# io-board-d-2.net
KiCad netlist of a schematic drawn in EAGLE
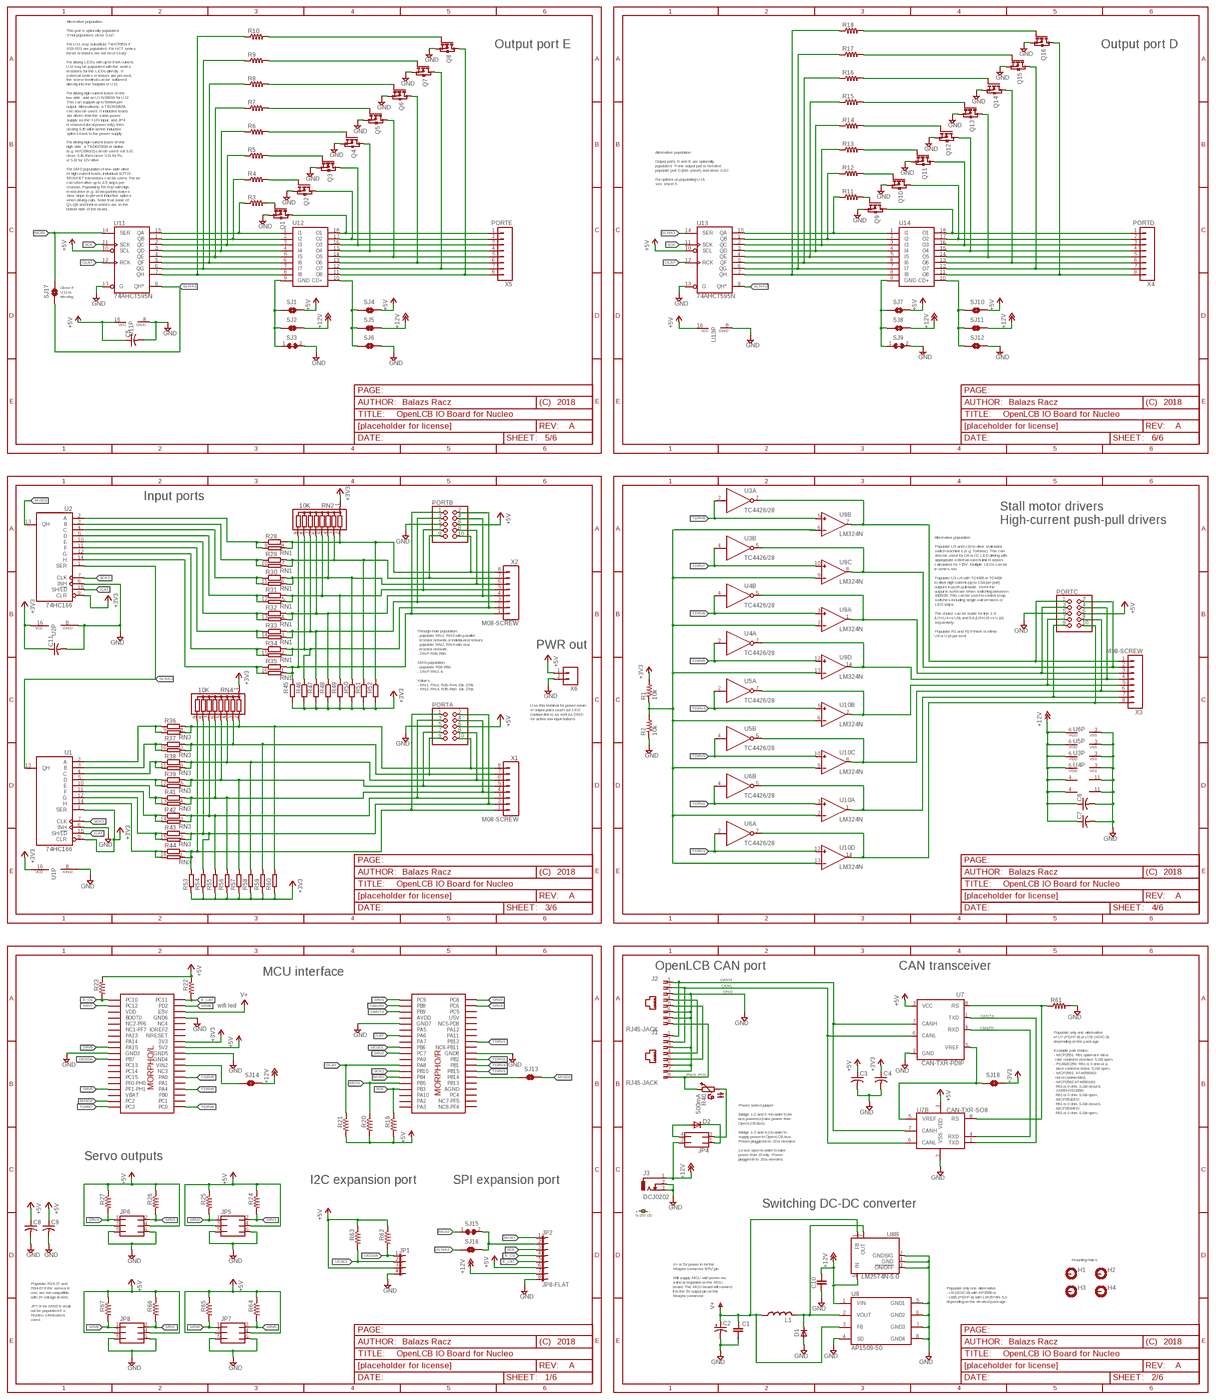
[diagram p0: schematic, sheet 1, overview]
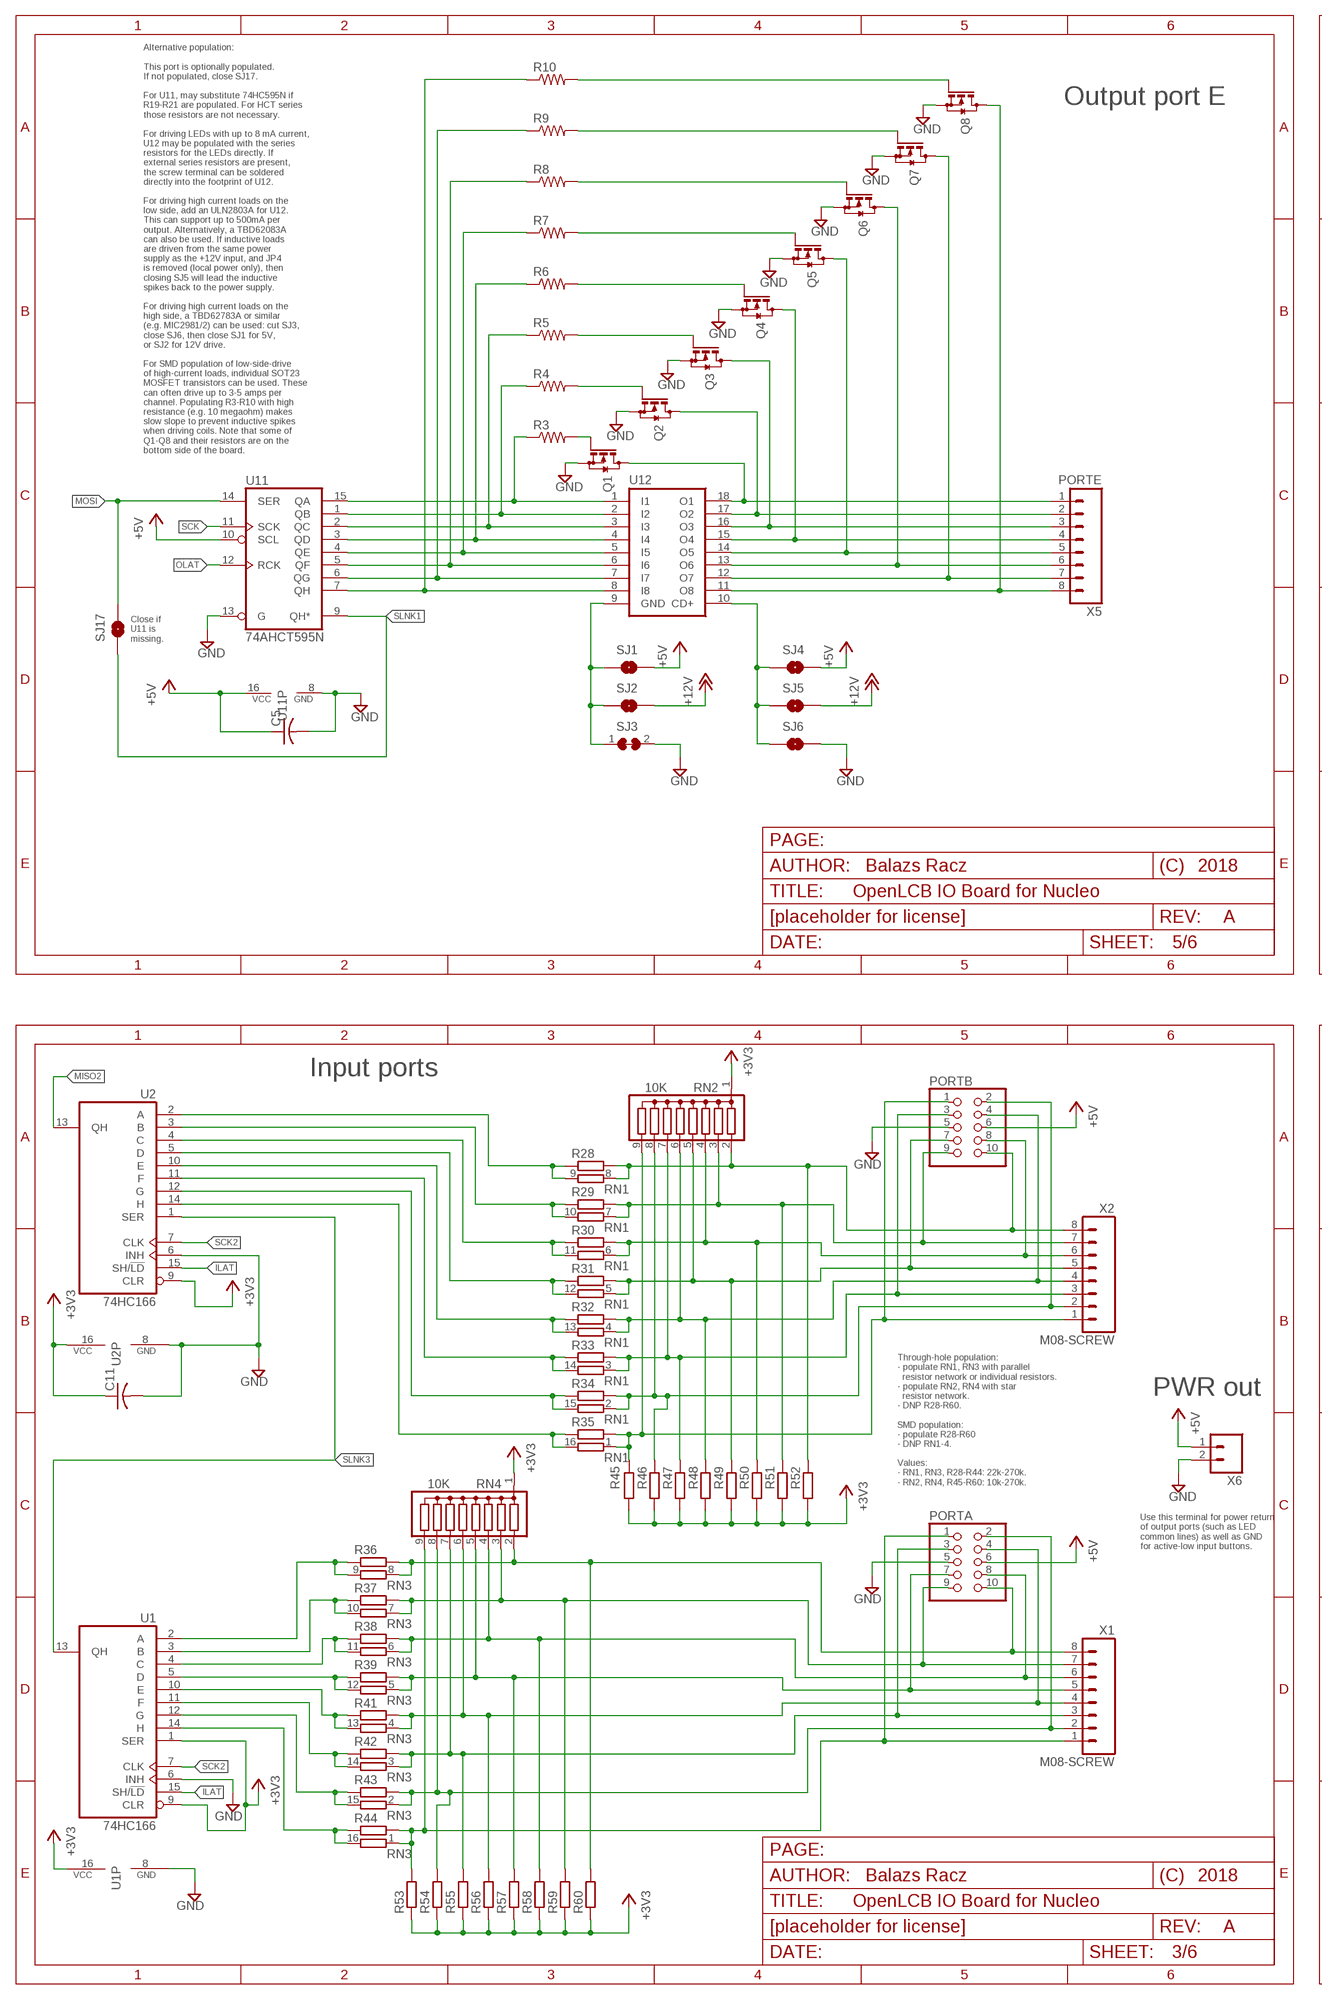
[diagram p1: schematic, sheet 1, part 1 of 4]
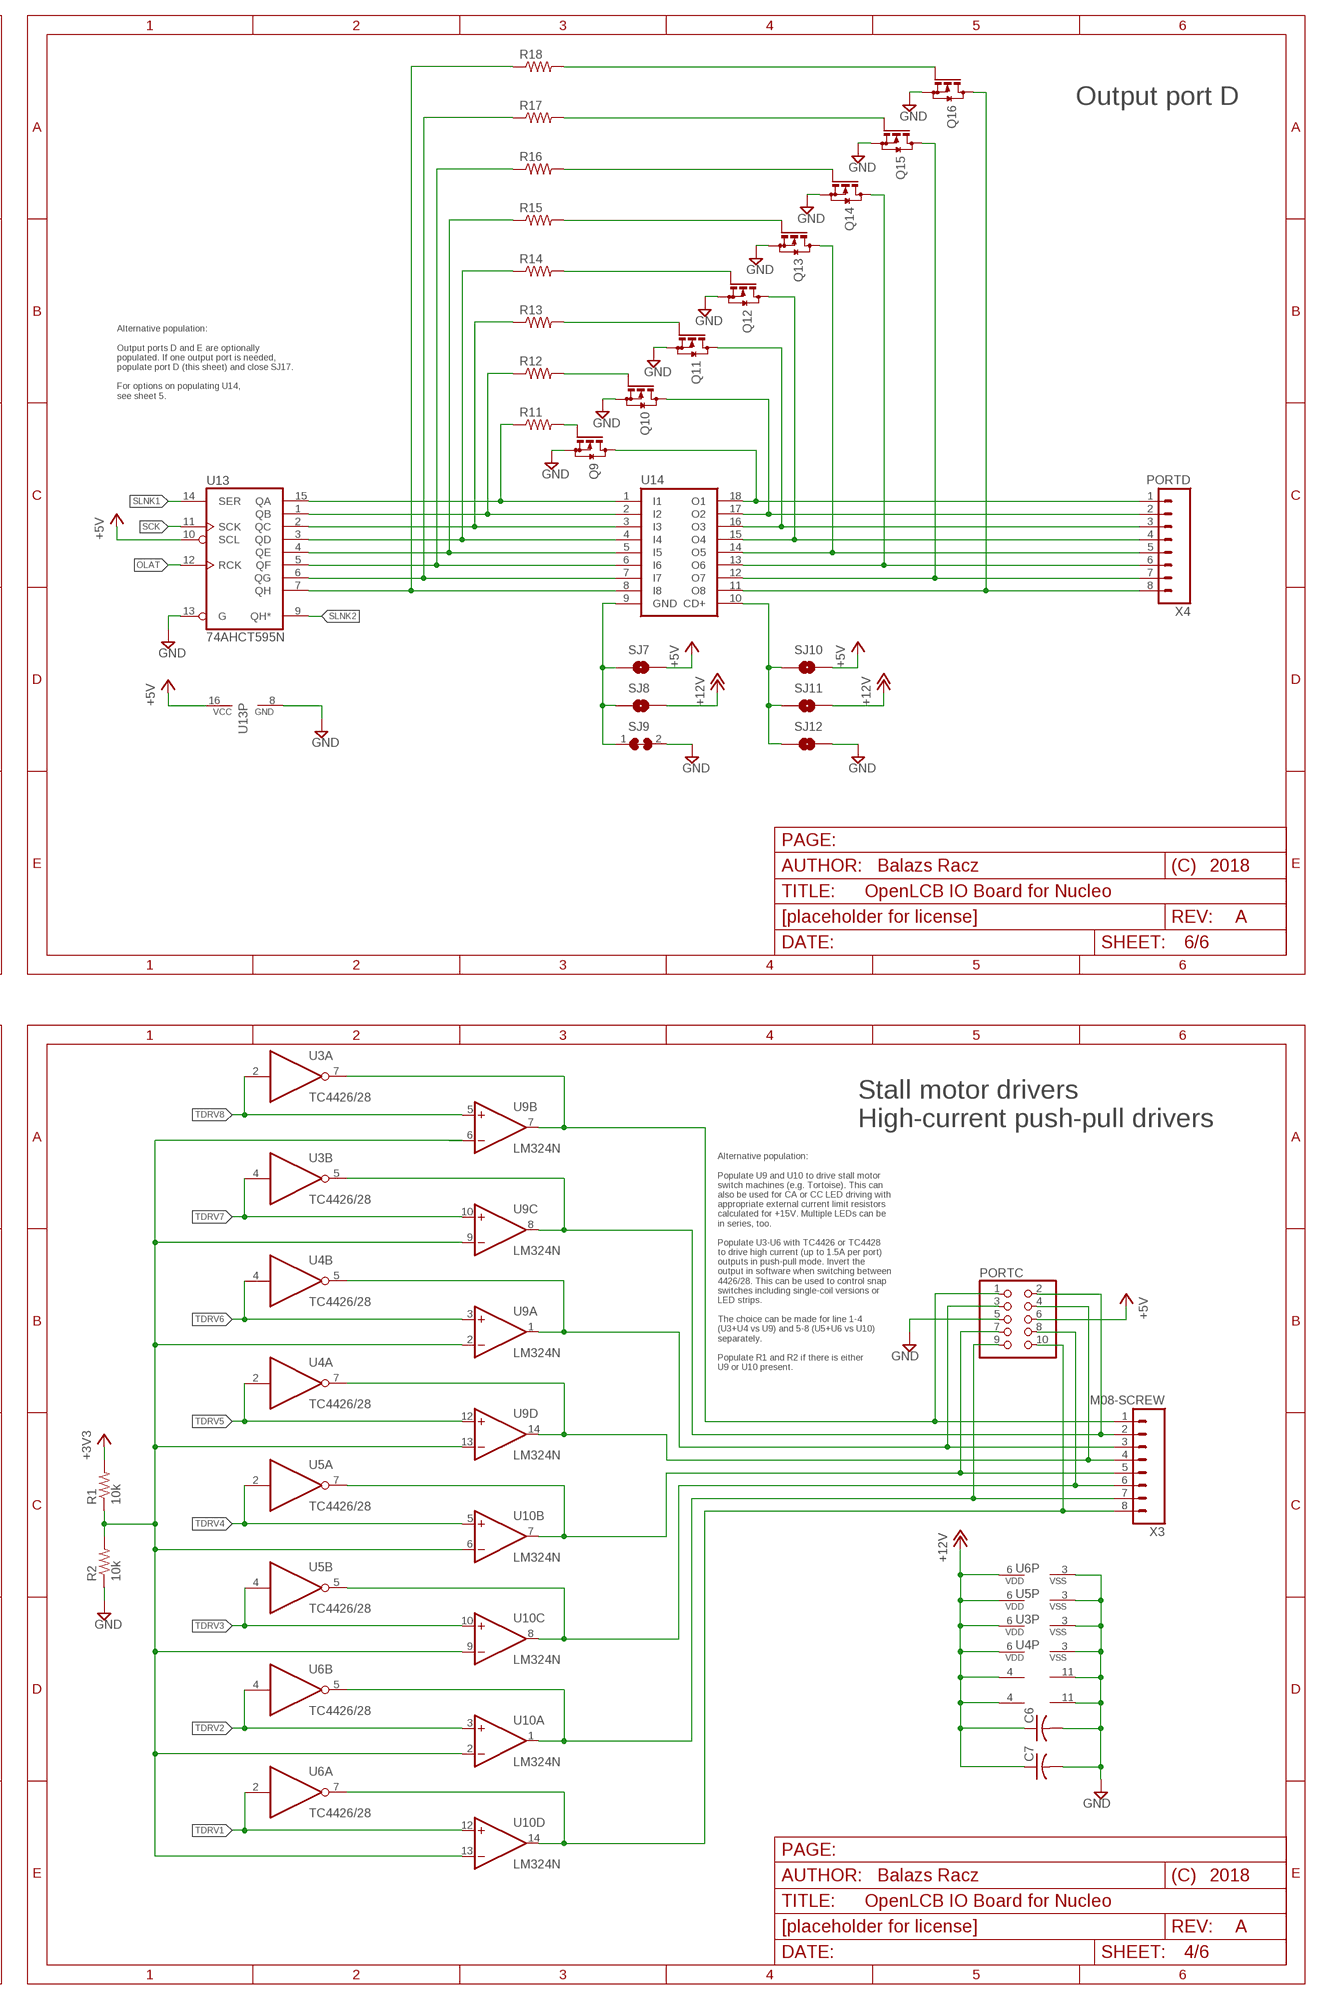
[diagram p2: schematic, sheet 1, part 2 of 4]
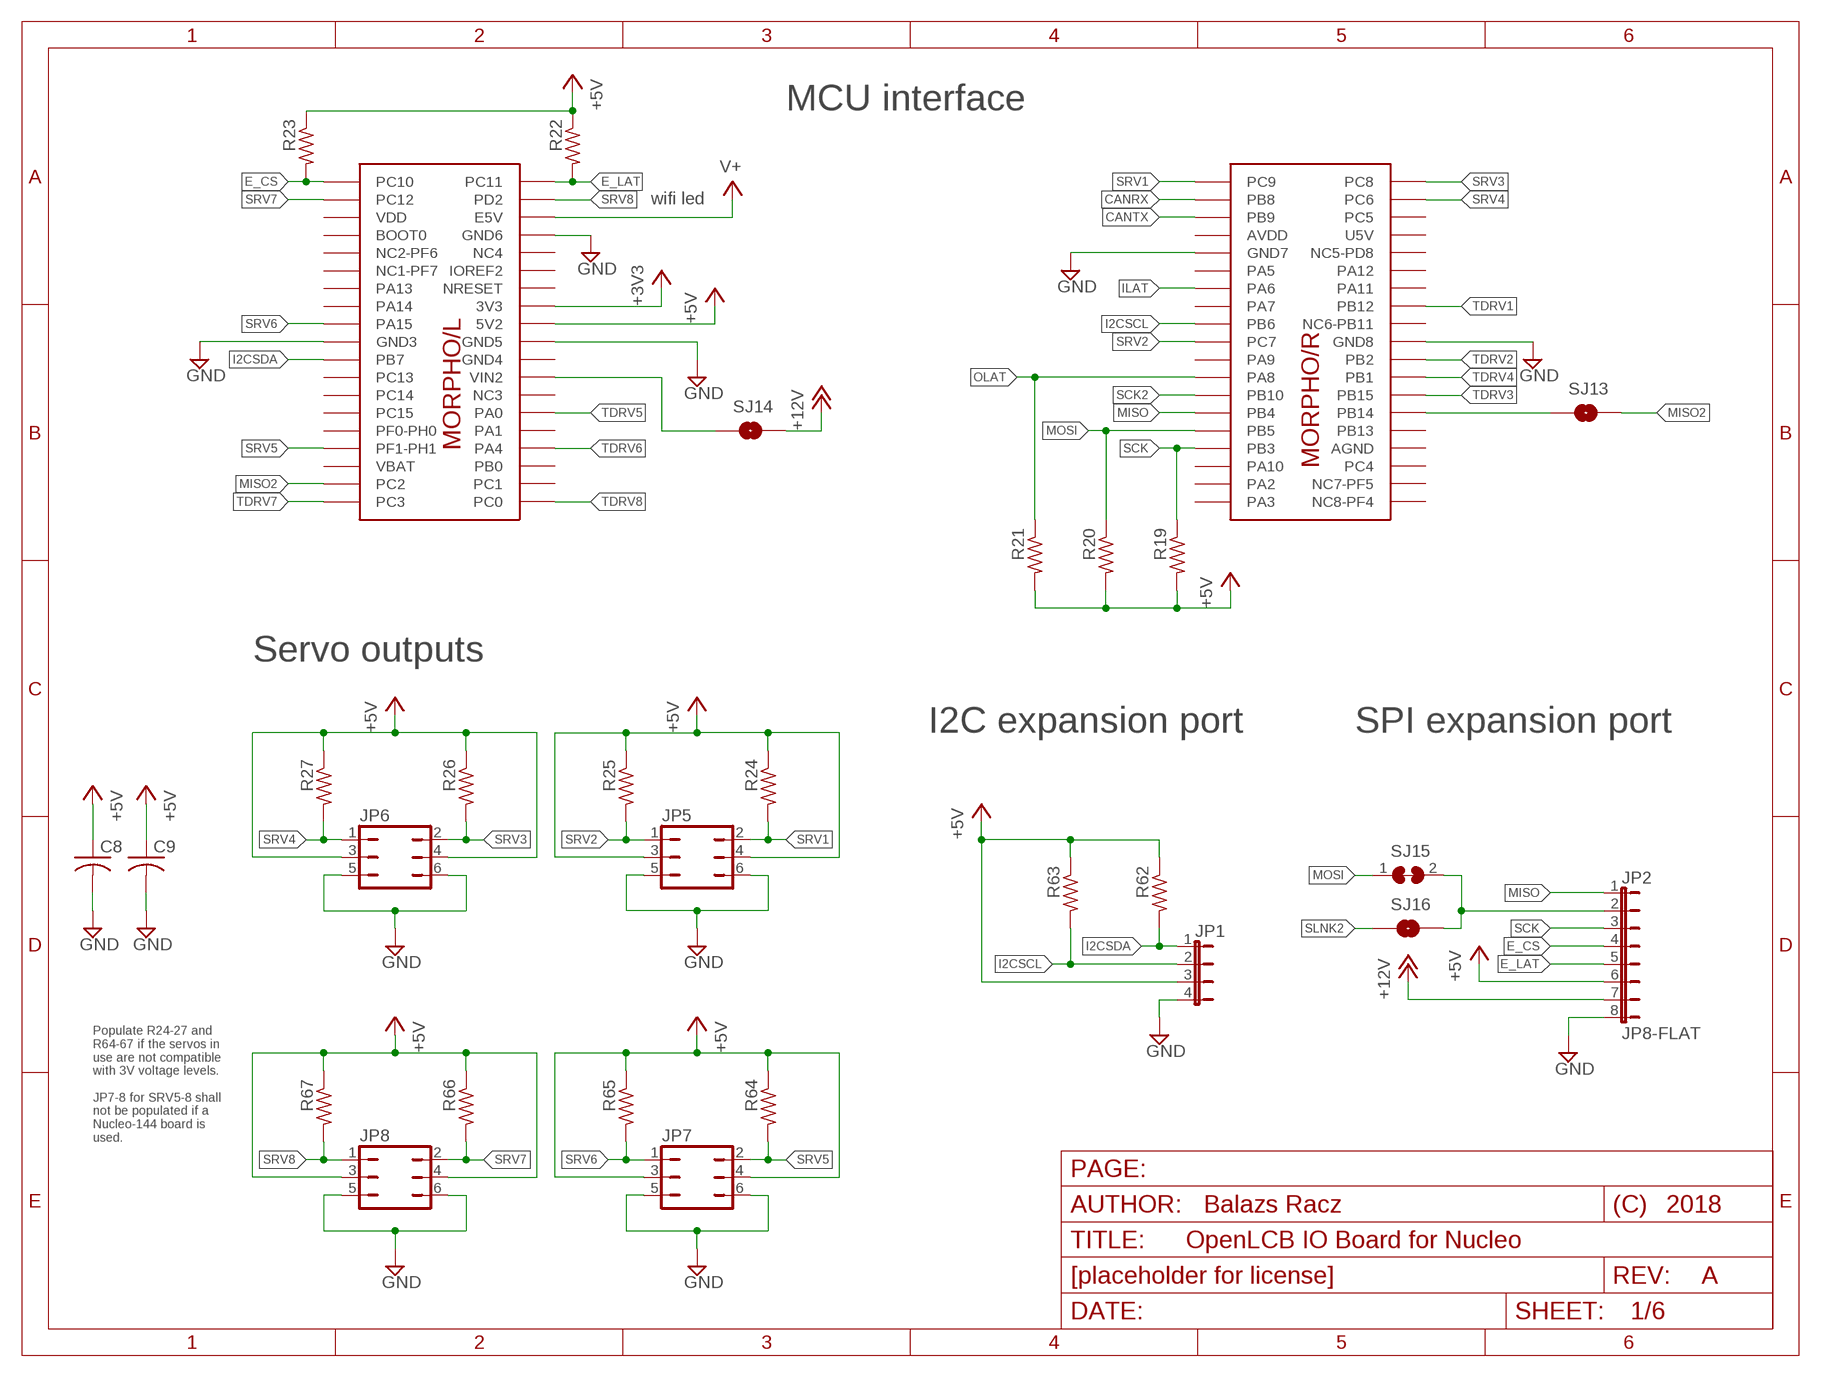
[diagram p3: schematic, sheet 1, part 3 of 4]
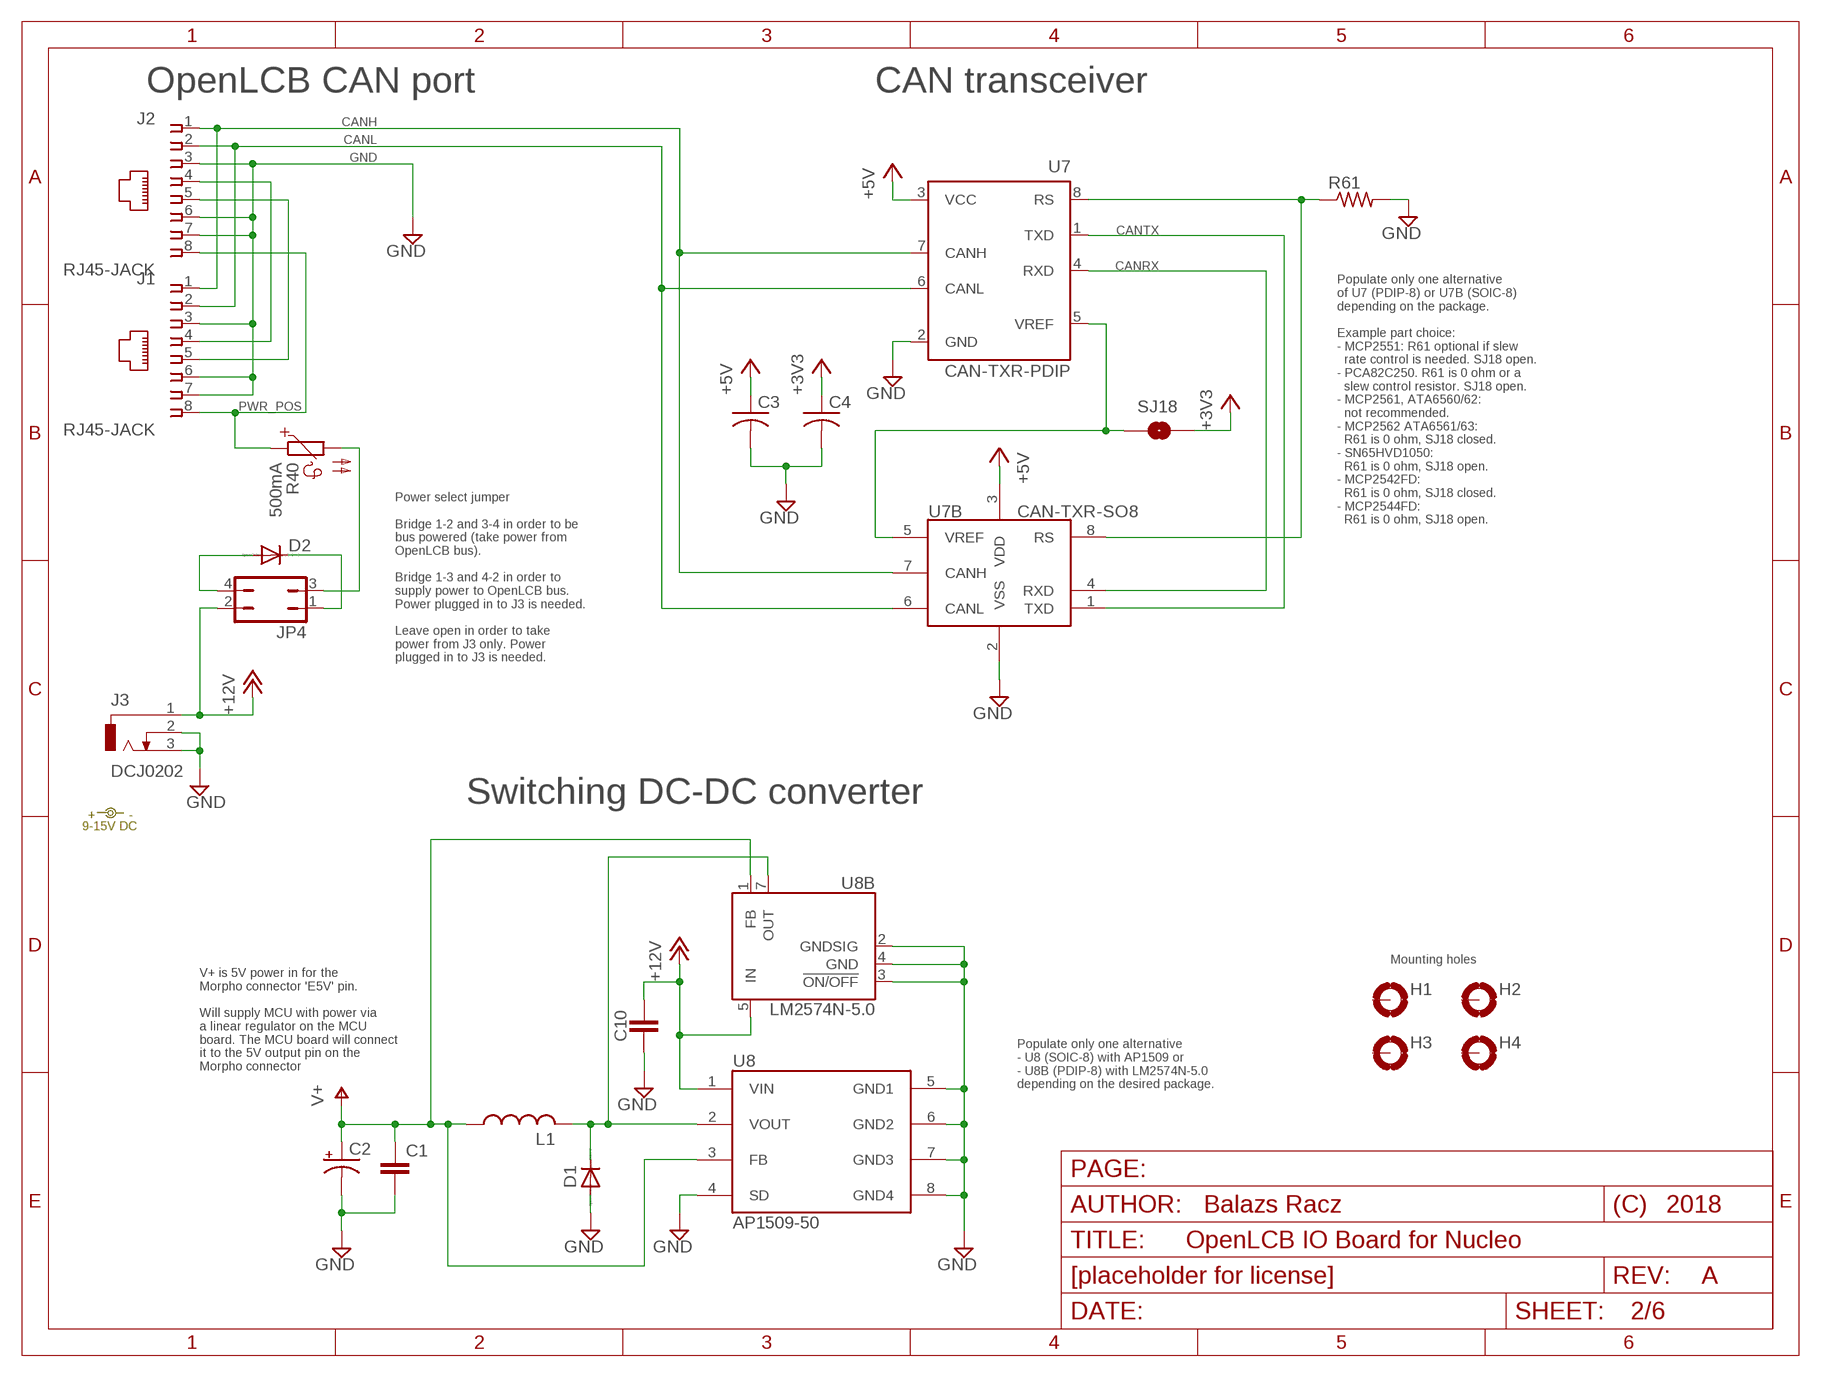
[diagram p4: schematic, sheet 1, part 4 of 4]

(export (version "E")
  (design (tool "Eeschema 10.0.6"))
  (components
    (comp (ref "+12V")
      (value "9-15V DC")
      (footprint "eagle-import:POWER_USAGE")
      (libsource (lib "eagle-import") (part "DOC-POWER_LABEL"))
    )
    (comp (ref "C1")
      (value "C-EUC1206")
      (footprint "eagle-import:C1206")
      (libsource (lib "eagle-import") (part "C-EUC1206"))
    )
    (comp (ref "C2")
      (value "CPOL-USE2.5-5")
      (footprint "eagle-import:E2,5-5")
      (libsource (lib "eagle-import") (part "CPOL-USE2.5-5"))
    )
    (comp (ref "C3")
      (value "C-USC0805")
      (footprint "eagle-import:C0805")
      (libsource (lib "eagle-import") (part "C-USC0805"))
    )
    (comp (ref "C4")
      (value "C-USC0805")
      (footprint "eagle-import:C0805")
      (libsource (lib "eagle-import") (part "C-USC0805"))
    )
    (comp (ref "C5")
      (value "C-USC0805")
      (footprint "eagle-import:C0805")
      (libsource (lib "eagle-import") (part "C-USC0805"))
    )
    (comp (ref "C6")
      (value "C-USC1206")
      (footprint "eagle-import:C1206")
      (libsource (lib "eagle-import") (part "C-USC1206"))
    )
    (comp (ref "C7")
      (value "C-USC1206")
      (footprint "eagle-import:C1206")
      (libsource (lib "eagle-import") (part "C-USC1206"))
    )
    (comp (ref "C8")
      (value "C-USC1206")
      (footprint "eagle-import:C1206")
      (libsource (lib "eagle-import") (part "C-USC1206"))
    )
    (comp (ref "C9")
      (value "C-USC1206")
      (footprint "eagle-import:C1206")
      (libsource (lib "eagle-import") (part "C-USC1206"))
    )
    (comp (ref "C10")
      (value "C-EUC1206")
      (footprint "eagle-import:C1206")
      (libsource (lib "eagle-import") (part "C-EUC1206"))
    )
    (comp (ref "C11")
      (value "C-USC0805")
      (footprint "eagle-import:C0805")
      (libsource (lib "eagle-import") (part "C-USC0805"))
    )
    (comp (ref "D1")
      (value "DIODE-DO41-7.6")
      (footprint "eagle-import:DO41-7.6")
      (libsource (lib "eagle-import") (part "DIODE-DO41-7.6"))
    )
    (comp (ref "D2")
      (value "DIODE-DO41-7.6")
      (footprint "eagle-import:DO41-7.6")
      (libsource (lib "eagle-import") (part "DIODE-DO41-7.6"))
    )
    (comp (ref "H1")
      (value "MOUNT-PAD-ROUND3.3")
      (footprint "eagle-import:3,3-PAD")
      (libsource (lib "eagle-import") (part "MOUNT-PAD-ROUND3.3"))
    )
    (comp (ref "H2")
      (value "MOUNT-PAD-ROUND3.3")
      (footprint "eagle-import:3,3-PAD")
      (libsource (lib "eagle-import") (part "MOUNT-PAD-ROUND3.3"))
    )
    (comp (ref "H3")
      (value "MOUNT-PAD-ROUND3.3")
      (footprint "eagle-import:3,3-PAD")
      (libsource (lib "eagle-import") (part "MOUNT-PAD-ROUND3.3"))
    )
    (comp (ref "H4")
      (value "MOUNT-PAD-ROUND3.3")
      (footprint "eagle-import:3,3-PAD")
      (libsource (lib "eagle-import") (part "MOUNT-PAD-ROUND3.3"))
    )
    (comp (ref "J1")
      (value "RJ45-JACK")
      (footprint "eagle-import:RJ45-PULSE-E5J88")
      (libsource (lib "eagle-import") (part "RJ45-JACKRJ45-PULSE-E5J00"))
    )
    (comp (ref "J2")
      (value "RJ45-JACK")
      (footprint "eagle-import:RJ45-PULSE-E5J88")
      (libsource (lib "eagle-import") (part "RJ45-JACKRJ45-PULSE-E5J00"))
    )
    (comp (ref "J3")
      (value "DCJ0202")
      (footprint "eagle-import:DCJ0202")
      (libsource (lib "eagle-import") (part "DCJ0202"))
    )
    (comp (ref "JP1")
      (value "JP4-FLAT")
      (footprint "eagle-import:JP4F")
      (libsource (lib "eagle-import") (part "JP4-FLAT"))
    )
    (comp (ref "JP2")
      (value "JP8-FLAT")
      (footprint "eagle-import:JP8F")
      (libsource (lib "eagle-import") (part "JP8-FLAT"))
    )
    (comp (ref "JP4")
      (value "JP2Q")
      (footprint "eagle-import:JP2Q")
      (libsource (lib "eagle-import") (part "JP2Q"))
    )
    (comp (ref "JP5")
      (value "JP3Q")
      (footprint "eagle-import:JP3Q")
      (libsource (lib "eagle-import") (part "JP3Q"))
    )
    (comp (ref "JP6")
      (value "JP3Q")
      (footprint "eagle-import:JP3Q")
      (libsource (lib "eagle-import") (part "JP3Q"))
    )
    (comp (ref "JP7")
      (value "JP3Q")
      (footprint "eagle-import:JP3Q")
      (libsource (lib "eagle-import") (part "JP3Q"))
    )
    (comp (ref "JP8")
      (value "JP3Q")
      (footprint "eagle-import:JP3Q")
      (libsource (lib "eagle-import") (part "JP3Q"))
    )
    (comp (ref "L1")
      (value "L-US")
      (footprint "eagle-import:L5-8,5")
      (libsource (lib "eagle-import") (part "L-US"))
    )
    (comp (ref "PORTA")
      (value "PINHD-2X5CN")
      (footprint "eagle-import:CON10M")
      (libsource (lib "eagle-import") (part "PINHD-2X5CN"))
    )
    (comp (ref "PORTB")
      (value "PINHD-2X5CN")
      (footprint "eagle-import:CON10M")
      (libsource (lib "eagle-import") (part "PINHD-2X5CN"))
    )
    (comp (ref "PORTC")
      (value "PINHD-2X5CN")
      (footprint "eagle-import:CON10M")
      (libsource (lib "eagle-import") (part "PINHD-2X5CN"))
    )
    (comp (ref "Q1")
      (value "BSS123")
      (footprint "eagle-import:SOT23")
      (libsource (lib "eagle-import") (part "BSS123"))
    )
    (comp (ref "Q2")
      (value "BSS123")
      (footprint "eagle-import:SOT23")
      (libsource (lib "eagle-import") (part "BSS123"))
    )
    (comp (ref "Q3")
      (value "BSS123")
      (footprint "eagle-import:SOT23")
      (libsource (lib "eagle-import") (part "BSS123"))
    )
    (comp (ref "Q4")
      (value "BSS123")
      (footprint "eagle-import:SOT23")
      (libsource (lib "eagle-import") (part "BSS123"))
    )
    (comp (ref "Q5")
      (value "BSS123")
      (footprint "eagle-import:SOT23")
      (libsource (lib "eagle-import") (part "BSS123"))
    )
    (comp (ref "Q6")
      (value "BSS123")
      (footprint "eagle-import:SOT23")
      (libsource (lib "eagle-import") (part "BSS123"))
    )
    (comp (ref "Q7")
      (value "BSS123")
      (footprint "eagle-import:SOT23")
      (libsource (lib "eagle-import") (part "BSS123"))
    )
    (comp (ref "Q8")
      (value "BSS123")
      (footprint "eagle-import:SOT23")
      (libsource (lib "eagle-import") (part "BSS123"))
    )
    (comp (ref "Q9")
      (value "BSS123")
      (footprint "eagle-import:SOT23")
      (libsource (lib "eagle-import") (part "BSS123"))
    )
    (comp (ref "Q10")
      (value "BSS123")
      (footprint "eagle-import:SOT23")
      (libsource (lib "eagle-import") (part "BSS123"))
    )
    (comp (ref "Q11")
      (value "BSS123")
      (footprint "eagle-import:SOT23")
      (libsource (lib "eagle-import") (part "BSS123"))
    )
    (comp (ref "Q12")
      (value "BSS123")
      (footprint "eagle-import:SOT23")
      (libsource (lib "eagle-import") (part "BSS123"))
    )
    (comp (ref "Q13")
      (value "BSS123")
      (footprint "eagle-import:SOT23")
      (libsource (lib "eagle-import") (part "BSS123"))
    )
    (comp (ref "Q14")
      (value "BSS123")
      (footprint "eagle-import:SOT23")
      (libsource (lib "eagle-import") (part "BSS123"))
    )
    (comp (ref "Q15")
      (value "BSS123")
      (footprint "eagle-import:SOT23")
      (libsource (lib "eagle-import") (part "BSS123"))
    )
    (comp (ref "Q16")
      (value "BSS123")
      (footprint "eagle-import:SOT23")
      (libsource (lib "eagle-import") (part "BSS123"))
    )
    (comp (ref "R1")
      (value "10k")
      (footprint "eagle-import:R0805")
      (libsource (lib "eagle-import") (part "R-US_R0805"))
    )
    (comp (ref "R2")
      (value "10k")
      (footprint "eagle-import:R0805")
      (libsource (lib "eagle-import") (part "R-US_R0805"))
    )
    (comp (ref "R3")
      (value "R-US_R0603")
      (footprint "eagle-import:R0603")
      (libsource (lib "eagle-import") (part "R-US_R0603"))
    )
    (comp (ref "R4")
      (value "R-US_R0603")
      (footprint "eagle-import:R0603")
      (libsource (lib "eagle-import") (part "R-US_R0603"))
    )
    (comp (ref "R5")
      (value "R-US_R0603")
      (footprint "eagle-import:R0603")
      (libsource (lib "eagle-import") (part "R-US_R0603"))
    )
    (comp (ref "R6")
      (value "R-US_R0603")
      (footprint "eagle-import:R0603")
      (libsource (lib "eagle-import") (part "R-US_R0603"))
    )
    (comp (ref "R7")
      (value "R-US_R0603")
      (footprint "eagle-import:R0603")
      (libsource (lib "eagle-import") (part "R-US_R0603"))
    )
    (comp (ref "R8")
      (value "R-US_R0603")
      (footprint "eagle-import:R0603")
      (libsource (lib "eagle-import") (part "R-US_R0603"))
    )
    (comp (ref "R9")
      (value "R-US_R0603")
      (footprint "eagle-import:R0603")
      (libsource (lib "eagle-import") (part "R-US_R0603"))
    )
    (comp (ref "R10")
      (value "R-US_R0603")
      (footprint "eagle-import:R0603")
      (libsource (lib "eagle-import") (part "R-US_R0603"))
    )
    (comp (ref "R11")
      (value "R-US_R0603")
      (footprint "eagle-import:R0603")
      (libsource (lib "eagle-import") (part "R-US_R0603"))
    )
    (comp (ref "R12")
      (value "R-US_R0603")
      (footprint "eagle-import:R0603")
      (libsource (lib "eagle-import") (part "R-US_R0603"))
    )
    (comp (ref "R13")
      (value "R-US_R0603")
      (footprint "eagle-import:R0603")
      (libsource (lib "eagle-import") (part "R-US_R0603"))
    )
    (comp (ref "R14")
      (value "R-US_R0603")
      (footprint "eagle-import:R0603")
      (libsource (lib "eagle-import") (part "R-US_R0603"))
    )
    (comp (ref "R15")
      (value "R-US_R0603")
      (footprint "eagle-import:R0603")
      (libsource (lib "eagle-import") (part "R-US_R0603"))
    )
    (comp (ref "R16")
      (value "R-US_R0603")
      (footprint "eagle-import:R0603")
      (libsource (lib "eagle-import") (part "R-US_R0603"))
    )
    (comp (ref "R17")
      (value "R-US_R0603")
      (footprint "eagle-import:R0603")
      (libsource (lib "eagle-import") (part "R-US_R0603"))
    )
    (comp (ref "R18")
      (value "R-US_R0603")
      (footprint "eagle-import:R0603")
      (libsource (lib "eagle-import") (part "R-US_R0603"))
    )
    (comp (ref "R19")
      (value "R-US_R0805")
      (footprint "eagle-import:R0805")
      (libsource (lib "eagle-import") (part "rcl_334_R-US_R0805"))
    )
    (comp (ref "R20")
      (value "R-US_R0805")
      (footprint "eagle-import:R0805")
      (libsource (lib "eagle-import") (part "rcl_334_R-US_R0805"))
    )
    (comp (ref "R21")
      (value "R-US_R0805")
      (footprint "eagle-import:R0805")
      (libsource (lib "eagle-import") (part "rcl_334_R-US_R0805"))
    )
    (comp (ref "R22")
      (value "R-US_R0805")
      (footprint "eagle-import:R0805")
      (libsource (lib "eagle-import") (part "rcl_334_R-US_R0805"))
    )
    (comp (ref "R23")
      (value "R-US_R0805")
      (footprint "eagle-import:R0805")
      (libsource (lib "eagle-import") (part "rcl_334_R-US_R0805"))
    )
    (comp (ref "R24")
      (value "R-US_R0805")
      (footprint "eagle-import:R0805")
      (libsource (lib "eagle-import") (part "rcl_334_R-US_R0805"))
    )
    (comp (ref "R25")
      (value "R-US_R0805")
      (footprint "eagle-import:R0805")
      (libsource (lib "eagle-import") (part "rcl_334_R-US_R0805"))
    )
    (comp (ref "R26")
      (value "R-US_R0805")
      (footprint "eagle-import:R0805")
      (libsource (lib "eagle-import") (part "rcl_334_R-US_R0805"))
    )
    (comp (ref "R27")
      (value "R-US_R0805")
      (footprint "eagle-import:R0805")
      (libsource (lib "eagle-import") (part "rcl_334_R-US_R0805"))
    )
    (comp (ref "R28")
      (value "R-EU_R0603")
      (footprint "eagle-import:R0603")
      (libsource (lib "eagle-import") (part "R-EU_R0603"))
    )
    (comp (ref "R29")
      (value "R-EU_R0603")
      (footprint "eagle-import:R0603")
      (libsource (lib "eagle-import") (part "R-EU_R0603"))
    )
    (comp (ref "R30")
      (value "R-EU_R0603")
      (footprint "eagle-import:R0603")
      (libsource (lib "eagle-import") (part "R-EU_R0603"))
    )
    (comp (ref "R31")
      (value "R-EU_R0603")
      (footprint "eagle-import:R0603")
      (libsource (lib "eagle-import") (part "R-EU_R0603"))
    )
    (comp (ref "R32")
      (value "R-EU_R0603")
      (footprint "eagle-import:R0603")
      (libsource (lib "eagle-import") (part "R-EU_R0603"))
    )
    (comp (ref "R33")
      (value "R-EU_R0603")
      (footprint "eagle-import:R0603")
      (libsource (lib "eagle-import") (part "R-EU_R0603"))
    )
    (comp (ref "R34")
      (value "R-EU_R0603")
      (footprint "eagle-import:R0603")
      (libsource (lib "eagle-import") (part "R-EU_R0603"))
    )
    (comp (ref "R35")
      (value "R-EU_R0603")
      (footprint "eagle-import:R0603")
      (libsource (lib "eagle-import") (part "R-EU_R0603"))
    )
    (comp (ref "R36")
      (value "R-EU_R0603")
      (footprint "eagle-import:R0603")
      (libsource (lib "eagle-import") (part "R-EU_R0603"))
    )
    (comp (ref "R37")
      (value "R-EU_R0603")
      (footprint "eagle-import:R0603")
      (libsource (lib "eagle-import") (part "R-EU_R0603"))
    )
    (comp (ref "R38")
      (value "R-EU_R0603")
      (footprint "eagle-import:R0603")
      (libsource (lib "eagle-import") (part "R-EU_R0603"))
    )
    (comp (ref "R39")
      (value "R-EU_R0603")
      (footprint "eagle-import:R0603")
      (libsource (lib "eagle-import") (part "R-EU_R0603"))
    )
    (comp (ref "R40")
      (value "500mA")
      (footprint "eagle-import:PTC1812")
      (libsource (lib "eagle-import") (part "PTC_1812"))
    )
    (comp (ref "R41")
      (value "R-EU_R0603")
      (footprint "eagle-import:R0603")
      (libsource (lib "eagle-import") (part "R-EU_R0603"))
    )
    (comp (ref "R42")
      (value "R-EU_R0603")
      (footprint "eagle-import:R0603")
      (libsource (lib "eagle-import") (part "R-EU_R0603"))
    )
    (comp (ref "R43")
      (value "R-EU_R0603")
      (footprint "eagle-import:R0603")
      (libsource (lib "eagle-import") (part "R-EU_R0603"))
    )
    (comp (ref "R44")
      (value "R-EU_R0603")
      (footprint "eagle-import:R0603")
      (libsource (lib "eagle-import") (part "R-EU_R0603"))
    )
    (comp (ref "R45")
      (value "R-EU_R0603")
      (footprint "eagle-import:R0603")
      (libsource (lib "eagle-import") (part "R-EU_R0603"))
    )
    (comp (ref "R46")
      (value "R-EU_R0603")
      (footprint "eagle-import:R0603")
      (libsource (lib "eagle-import") (part "R-EU_R0603"))
    )
    (comp (ref "R47")
      (value "R-EU_R0603")
      (footprint "eagle-import:R0603")
      (libsource (lib "eagle-import") (part "R-EU_R0603"))
    )
    (comp (ref "R48")
      (value "R-EU_R0603")
      (footprint "eagle-import:R0603")
      (libsource (lib "eagle-import") (part "R-EU_R0603"))
    )
    (comp (ref "R49")
      (value "R-EU_R0603")
      (footprint "eagle-import:R0603")
      (libsource (lib "eagle-import") (part "R-EU_R0603"))
    )
    (comp (ref "R50")
      (value "R-EU_R0603")
      (footprint "eagle-import:R0603")
      (libsource (lib "eagle-import") (part "R-EU_R0603"))
    )
    (comp (ref "R51")
      (value "R-EU_R0603")
      (footprint "eagle-import:R0603")
      (libsource (lib "eagle-import") (part "R-EU_R0603"))
    )
    (comp (ref "R52")
      (value "R-EU_R0603")
      (footprint "eagle-import:R0603")
      (libsource (lib "eagle-import") (part "R-EU_R0603"))
    )
    (comp (ref "R53")
      (value "R-EU_R0603")
      (footprint "eagle-import:R0603")
      (libsource (lib "eagle-import") (part "R-EU_R0603"))
    )
    (comp (ref "R54")
      (value "R-EU_R0603")
      (footprint "eagle-import:R0603")
      (libsource (lib "eagle-import") (part "R-EU_R0603"))
    )
    (comp (ref "R55")
      (value "R-EU_R0603")
      (footprint "eagle-import:R0603")
      (libsource (lib "eagle-import") (part "R-EU_R0603"))
    )
    (comp (ref "R56")
      (value "R-EU_R0603")
      (footprint "eagle-import:R0603")
      (libsource (lib "eagle-import") (part "R-EU_R0603"))
    )
    (comp (ref "R57")
      (value "R-EU_R0603")
      (footprint "eagle-import:R0603")
      (libsource (lib "eagle-import") (part "R-EU_R0603"))
    )
    (comp (ref "R58")
      (value "R-EU_R0603")
      (footprint "eagle-import:R0603")
      (libsource (lib "eagle-import") (part "R-EU_R0603"))
    )
    (comp (ref "R59")
      (value "R-EU_R0603")
      (footprint "eagle-import:R0603")
      (libsource (lib "eagle-import") (part "R-EU_R0603"))
    )
    (comp (ref "R60")
      (value "R-EU_R0603")
      (footprint "eagle-import:R0603")
      (libsource (lib "eagle-import") (part "R-EU_R0603"))
    )
    (comp (ref "R61")
      (value "R-US_R0805")
      (footprint "eagle-import:R0805")
      (libsource (lib "eagle-import") (part "rcl_334_R-US_R0805"))
    )
    (comp (ref "R62")
      (value "R-US_R0805")
      (footprint "eagle-import:R0805")
      (libsource (lib "eagle-import") (part "rcl_334_R-US_R0805"))
    )
    (comp (ref "R63")
      (value "R-US_R0805")
      (footprint "eagle-import:R0805")
      (libsource (lib "eagle-import") (part "rcl_334_R-US_R0805"))
    )
    (comp (ref "R64")
      (value "R-US_R0805")
      (footprint "eagle-import:R0805")
      (libsource (lib "eagle-import") (part "rcl_334_R-US_R0805"))
    )
    (comp (ref "R65")
      (value "R-US_R0805")
      (footprint "eagle-import:R0805")
      (libsource (lib "eagle-import") (part "rcl_334_R-US_R0805"))
    )
    (comp (ref "R66")
      (value "R-US_R0805")
      (footprint "eagle-import:R0805")
      (libsource (lib "eagle-import") (part "rcl_334_R-US_R0805"))
    )
    (comp (ref "R67")
      (value "R-US_R0805")
      (footprint "eagle-import:R0805")
      (libsource (lib "eagle-import") (part "rcl_334_R-US_R0805"))
    )
    (comp (ref "RN1")
      (value "8R-P")
      (footprint "eagle-import:DIL16")
      (libsource (lib "eagle-import") (part "8R-P"))
    )
    (comp (ref "RN2")
      (value "10K")
      (footprint "eagle-import:SIL9")
      (libsource (lib "eagle-import") (part "G08R"))
    )
    (comp (ref "RN3")
      (value "8R-P")
      (footprint "eagle-import:DIL16")
      (libsource (lib "eagle-import") (part "8R-P"))
    )
    (comp (ref "RN4")
      (value "10K")
      (footprint "eagle-import:SIL9")
      (libsource (lib "eagle-import") (part "G08R"))
    )
    (comp (ref "SJ1")
      (value "SJRND2")
      (footprint "eagle-import:SJ_RND2")
      (libsource (lib "eagle-import") (part "SJRND2"))
    )
    (comp (ref "SJ2")
      (value "SJRND2")
      (footprint "eagle-import:SJ_RND2")
      (libsource (lib "eagle-import") (part "SJRND2"))
    )
    (comp (ref "SJ3")
      (value "SJ-C")
      (footprint "eagle-import:SJW-C")
      (libsource (lib "eagle-import") (part "SJ-C"))
    )
    (comp (ref "SJ4")
      (value "SJRND2")
      (footprint "eagle-import:SJ_RND2")
      (libsource (lib "eagle-import") (part "SJRND2"))
    )
    (comp (ref "SJ5")
      (value "SJRND2")
      (footprint "eagle-import:SJ_RND2")
      (libsource (lib "eagle-import") (part "SJRND2"))
    )
    (comp (ref "SJ6")
      (value "SJRND2")
      (footprint "eagle-import:SJ_RND2")
      (libsource (lib "eagle-import") (part "SJRND2"))
    )
    (comp (ref "SJ7")
      (value "SJRND2")
      (footprint "eagle-import:SJ_RND2")
      (libsource (lib "eagle-import") (part "SJRND2"))
    )
    (comp (ref "SJ8")
      (value "SJRND2")
      (footprint "eagle-import:SJ_RND2")
      (libsource (lib "eagle-import") (part "SJRND2"))
    )
    (comp (ref "SJ9")
      (value "SJ-C")
      (footprint "eagle-import:SJW-C")
      (libsource (lib "eagle-import") (part "SJ-C"))
    )
    (comp (ref "SJ10")
      (value "SJRND2")
      (footprint "eagle-import:SJ_RND2")
      (libsource (lib "eagle-import") (part "SJRND2"))
    )
    (comp (ref "SJ11")
      (value "SJRND2")
      (footprint "eagle-import:SJ_RND2")
      (libsource (lib "eagle-import") (part "SJRND2"))
    )
    (comp (ref "SJ12")
      (value "SJRND2")
      (footprint "eagle-import:SJ_RND2")
      (libsource (lib "eagle-import") (part "SJRND2"))
    )
    (comp (ref "SJ13")
      (value "SJRND2")
      (footprint "eagle-import:SJ_RND2")
      (libsource (lib "eagle-import") (part "SJRND2"))
    )
    (comp (ref "SJ14")
      (value "SJRND2")
      (footprint "eagle-import:SJ_RND2")
      (libsource (lib "eagle-import") (part "SJRND2"))
    )
    (comp (ref "SJ15")
      (value "SJ-C")
      (footprint "eagle-import:SJW-C")
      (libsource (lib "eagle-import") (part "SJ-C"))
    )
    (comp (ref "SJ16")
      (value "SJRND2")
      (footprint "eagle-import:SJ_RND2")
      (libsource (lib "eagle-import") (part "SJRND2"))
    )
    (comp (ref "SJ17")
      (value "SJRND2")
      (footprint "eagle-import:SJ_RND2")
      (libsource (lib "eagle-import") (part "SJRND2"))
    )
    (comp (ref "SJ18")
      (value "SJRND2")
      (footprint "eagle-import:SJ_RND2")
      (libsource (lib "eagle-import") (part "SJRND2"))
    )
    (comp (ref "U$1")
      (value "NUCLEO_64_GENERIC")
      (footprint "eagle-import:NUCLEO_BRD_BASE64")
      (libsource (lib "eagle-import") (part "NUCLEO_64_GENERIC"))
    )
    (comp (ref "U1")
      (value "74HC166")
      (footprint "eagle-import:DIL16")
      (libsource (lib "eagle-import") (part "74166N"))
    )
    (comp (ref "U2")
      (value "74HC166")
      (footprint "eagle-import:DIL16")
      (libsource (lib "eagle-import") (part "74166N"))
    )
    (comp (ref "U3")
      (value "TC4426/28")
      (footprint "eagle-import:DIL08-LONG")
      (libsource (lib "eagle-import") (part "TC4426APDIP"))
    )
    (comp (ref "U4")
      (value "TC4426/28")
      (footprint "eagle-import:DIL08-LONG")
      (libsource (lib "eagle-import") (part "TC4426APDIP"))
    )
    (comp (ref "U5")
      (value "TC4426/28")
      (footprint "eagle-import:DIL08-LONG")
      (libsource (lib "eagle-import") (part "TC4426APDIP"))
    )
    (comp (ref "U6")
      (value "TC4426/28")
      (footprint "eagle-import:DIL08-LONG")
      (libsource (lib "eagle-import") (part "TC4426APDIP"))
    )
    (comp (ref "U7")
      (value "CAN-TXR-PDIP")
      (footprint "eagle-import:DIL08")
      (libsource (lib "eagle-import") (part "PCA82C250"))
    )
    (comp (ref "U7B")
      (value "CAN-TXR-SO8")
      (footprint "eagle-import:SO-08")
      (libsource (lib "eagle-import") (part "MCP2551-SN"))
    )
    (comp (ref "U8")
      (value "AP1509-50")
      (footprint "eagle-import:SO-08")
      (libsource (lib "eagle-import") (part "AP1509"))
    )
    (comp (ref "U8B")
      (value "LM2574N-5.0")
      (footprint "eagle-import:DIL08")
      (libsource (lib "eagle-import") (part "LM2574?-N5.0"))
    )
    (comp (ref "U9")
      (value "LM324N")
      (footprint "eagle-import:DIL14")
      (libsource (lib "eagle-import") (part "LM324N"))
    )
    (comp (ref "U10")
      (value "LM324N")
      (footprint "eagle-import:DIL14")
      (libsource (lib "eagle-import") (part "LM324N"))
    )
    (comp (ref "U11")
      (value "74AHCT595N")
      (footprint "eagle-import:DIL16")
      (libsource (lib "eagle-import") (part "74595NHCT"))
    )
    (comp (ref "U12")
      (value "ULN2803A")
      (footprint "eagle-import:DIL18-THIN")
      (libsource (lib "eagle-import") (part "ULN2803A"))
    )
    (comp (ref "U13")
      (value "74AHCT595N")
      (footprint "eagle-import:DIL16")
      (libsource (lib "eagle-import") (part "74595NHCT"))
    )
    (comp (ref "U14")
      (value "ULN2803A")
      (footprint "eagle-import:DIL18-THIN")
      (libsource (lib "eagle-import") (part "ULN2803A"))
    )
    (comp (ref "X1")
      (value "M08-SCREW")
      (footprint "eagle-import:1X08_TERMINAL")
      (libsource (lib "eagle-import") (part "M08-SCREW"))
    )
    (comp (ref "X2")
      (value "M08-SCREW")
      (footprint "eagle-import:1X08_TERMINAL")
      (libsource (lib "eagle-import") (part "M08-SCREW"))
    )
    (comp (ref "X3")
      (value "M08-SCREW")
      (footprint "eagle-import:1X08_TERMINAL")
      (libsource (lib "eagle-import") (part "M08-SCREW"))
    )
    (comp (ref "X4")
      (value "PORTD")
      (footprint "eagle-import:1X08_TERMINAL")
      (libsource (lib "eagle-import") (part "M08-SCREW"))
    )
    (comp (ref "X5")
      (value "PORTE")
      (footprint "eagle-import:1X08_TERMINAL")
      (libsource (lib "eagle-import") (part "M08-SCREW"))
    )
    (comp (ref "X6")
      (value "CONNECTOR-M023.5MM-LOCK")
      (footprint "eagle-import:SCREWTERMINAL-3.5MM-2_LOCK")
      (libsource (lib "eagle-import") (part "CONNECTOR-M023.5MM-LOCK"))
    )
  )
  (nets
    (net (code "1") (name "+3V3") (class "Default")
      (node (ref "C11") (pin "1") (pinfunction "1_1") (pintype "passive"))
      (node (ref "C4") (pin "1") (pinfunction "1_1") (pintype "passive"))
      (node (ref "R1") (pin "2") (pinfunction "2_2") (pintype "passive"))
      (node (ref "R45") (pin "1") (pinfunction "1_1") (pintype "passive"))
      (node (ref "R46") (pin "2") (pinfunction "2_2") (pintype "passive"))
      (node (ref "R47") (pin "2") (pinfunction "2_2") (pintype "passive"))
      (node (ref "R48") (pin "2") (pinfunction "2_2") (pintype "passive"))
      (node (ref "R49") (pin "2") (pinfunction "2_2") (pintype "passive"))
      (node (ref "R50") (pin "2") (pinfunction "2_2") (pintype "passive"))
      (node (ref "R51") (pin "2") (pinfunction "2_2") (pintype "passive"))
      (node (ref "R52") (pin "2") (pinfunction "2_2") (pintype "passive"))
      (node (ref "R53") (pin "1") (pinfunction "1_1") (pintype "passive"))
      (node (ref "R54") (pin "1") (pinfunction "1_1") (pintype "passive"))
      (node (ref "R55") (pin "1") (pinfunction "1_1") (pintype "passive"))
      (node (ref "R56") (pin "1") (pinfunction "1_1") (pintype "passive"))
      (node (ref "R57") (pin "1") (pinfunction "1_1") (pintype "passive"))
      (node (ref "R58") (pin "1") (pinfunction "1_1") (pintype "passive"))
      (node (ref "R59") (pin "1") (pinfunction "1_1") (pintype "passive"))
      (node (ref "R60") (pin "1") (pinfunction "1_1") (pintype "passive"))
      (node (ref "RN2") (pin "1") (pinfunction "1_1") (pintype "passive"))
      (node (ref "RN4") (pin "1") (pinfunction "1_1") (pintype "passive"))
      (node (ref "SJ18") (pin "P$1") (pinfunction "1_P$1") (pintype "passive"))
      (node (ref "U$1") (pin "3V3") (pinfunction "3V3_3V3") (pintype "power_in"))
      (node (ref "U1") (pin "1") (pinfunction "SER_1") (pintype "input"))
      (node (ref "U1") (pin "16") (pinfunction "VCC_16") (pintype "power_in"))
      (node (ref "U1") (pin "9") (pinfunction "CLR_9") (pintype "input"))
      (node (ref "U2") (pin "16") (pinfunction "VCC_16") (pintype "power_in"))
      (node (ref "U2") (pin "9") (pinfunction "CLR_9") (pintype "input"))
    )
    (net (code "2") (name "+5V") (class "Default")
      (node (ref "C3") (pin "1") (pinfunction "1_1") (pintype "passive"))
      (node (ref "C5") (pin "1") (pinfunction "1_1") (pintype "passive"))
      (node (ref "C8") (pin "1") (pinfunction "1_1") (pintype "passive"))
      (node (ref "C9") (pin "1") (pinfunction "1_1") (pintype "passive"))
      (node (ref "JP1") (pin "3") (pinfunction "3_3") (pintype "passive"))
      (node (ref "JP2") (pin "6") (pinfunction "6_6") (pintype "passive"))
      (node (ref "JP5") (pin "3") (pinfunction "3_3") (pintype "passive"))
      (node (ref "JP5") (pin "4") (pinfunction "4_4") (pintype "passive"))
      (node (ref "JP6") (pin "3") (pinfunction "3_3") (pintype "passive"))
      (node (ref "JP6") (pin "4") (pinfunction "4_4") (pintype "passive"))
      (node (ref "JP7") (pin "3") (pinfunction "3_3") (pintype "passive"))
      (node (ref "JP7") (pin "4") (pinfunction "4_4") (pintype "passive"))
      (node (ref "JP8") (pin "3") (pinfunction "3_3") (pintype "passive"))
      (node (ref "JP8") (pin "4") (pinfunction "4_4") (pintype "passive"))
      (node (ref "PORTA") (pin "6") (pinfunction "6_6") (pintype "passive"))
      (node (ref "PORTB") (pin "6") (pinfunction "6_6") (pintype "passive"))
      (node (ref "PORTC") (pin "6") (pinfunction "6_6") (pintype "passive"))
      (node (ref "R19") (pin "2") (pinfunction "2_2") (pintype "passive"))
      (node (ref "R20") (pin "2") (pinfunction "2_2") (pintype "passive"))
      (node (ref "R21") (pin "2") (pinfunction "2_2") (pintype "passive"))
      (node (ref "R22") (pin "1") (pinfunction "1_1") (pintype "passive"))
      (node (ref "R23") (pin "1") (pinfunction "1_1") (pintype "passive"))
      (node (ref "R24") (pin "1") (pinfunction "1_1") (pintype "passive"))
      (node (ref "R25") (pin "1") (pinfunction "1_1") (pintype "passive"))
      (node (ref "R26") (pin "1") (pinfunction "1_1") (pintype "passive"))
      (node (ref "R27") (pin "1") (pinfunction "1_1") (pintype "passive"))
      (node (ref "R62") (pin "1") (pinfunction "1_1") (pintype "passive"))
      (node (ref "R63") (pin "1") (pinfunction "1_1") (pintype "passive"))
      (node (ref "R64") (pin "1") (pinfunction "1_1") (pintype "passive"))
      (node (ref "R65") (pin "1") (pinfunction "1_1") (pintype "passive"))
      (node (ref "R66") (pin "1") (pinfunction "1_1") (pintype "passive"))
      (node (ref "R67") (pin "1") (pinfunction "1_1") (pintype "passive"))
      (node (ref "SJ1") (pin "P$2") (pinfunction "2_P$2") (pintype "passive"))
      (node (ref "SJ10") (pin "P$2") (pinfunction "2_P$2") (pintype "passive"))
      (node (ref "SJ4") (pin "P$2") (pinfunction "2_P$2") (pintype "passive"))
      (node (ref "SJ7") (pin "P$2") (pinfunction "2_P$2") (pintype "passive"))
      (node (ref "U$1") (pin "5V2") (pinfunction "5V2_5V2") (pintype "power_in"))
      (node (ref "U11") (pin "10") (pinfunction "SCL_10") (pintype "input"))
      (node (ref "U11") (pin "16") (pinfunction "VCC_16") (pintype "power_in"))
      (node (ref "U13") (pin "10") (pinfunction "SCL_10") (pintype "input"))
      (node (ref "U13") (pin "16") (pinfunction "VCC_16") (pintype "power_in"))
      (node (ref "U7") (pin "3") (pinfunction "VCC_3") (pintype "power_in"))
      (node (ref "U7B") (pin "3") (pinfunction "VDD_3") (pintype "power_in"))
      (node (ref "X6") (pin "1") (pinfunction "1_1") (pintype "passive"))
    )
    (net (code "3") (name "+12V") (class "Default")
      (node (ref "C10") (pin "1") (pinfunction "1_1") (pintype "passive"))
      (node (ref "C6") (pin "1") (pinfunction "1_1") (pintype "passive"))
      (node (ref "C7") (pin "1") (pinfunction "1_1") (pintype "passive"))
      (node (ref "J3") (pin "1") (pinfunction "1_1") (pintype "passive"))
      (node (ref "JP2") (pin "7") (pinfunction "7_7") (pintype "passive"))
      (node (ref "JP4") (pin "2") (pinfunction "2_2") (pintype "passive"))
      (node (ref "SJ11") (pin "P$2") (pinfunction "2_P$2") (pintype "passive"))
      (node (ref "SJ14") (pin "P$2") (pinfunction "2_P$2") (pintype "passive"))
      (node (ref "SJ2") (pin "P$2") (pinfunction "2_P$2") (pintype "passive"))
      (node (ref "SJ5") (pin "P$2") (pinfunction "2_P$2") (pintype "passive"))
      (node (ref "SJ8") (pin "P$2") (pinfunction "2_P$2") (pintype "passive"))
      (node (ref "U10") (pin "4") (pinfunction "V+_4") (pintype "power_in"))
      (node (ref "U3") (pin "6") (pinfunction "VDD_6") (pintype "power_in"))
      (node (ref "U4") (pin "6") (pinfunction "VDD_6") (pintype "power_in"))
      (node (ref "U5") (pin "6") (pinfunction "VDD_6") (pintype "power_in"))
      (node (ref "U6") (pin "6") (pinfunction "VDD_6") (pintype "power_in"))
      (node (ref "U8") (pin "1") (pinfunction "VIN_1") (pintype "bidirectional"))
      (node (ref "U8B") (pin "5") (pinfunction "IN_5") (pintype "input"))
      (node (ref "U9") (pin "4") (pinfunction "V+_4") (pintype "power_in"))
    )
    (net (code "4") (name "/AGND") (class "Default")
      (node (ref "U$1") (pin "AGND") (pinfunction "AGND_AGND") (pintype "power_in"))
    )
    (net (code "5") (name "/AVDD") (class "Default")
      (node (ref "U$1") (pin "AVDD") (pinfunction "AVDD_AVDD") (pintype "power_in"))
    )
    (net (code "6") (name "/CANH") (class "Default")
      (node (ref "J1") (pin "1") (pinfunction "1_1") (pintype "passive"))
      (node (ref "J2") (pin "1") (pinfunction "1_1") (pintype "passive"))
      (node (ref "U7") (pin "7") (pinfunction "CANH_7") (pintype "bidirectional"))
      (node (ref "U7B") (pin "7") (pinfunction "CANH_7") (pintype "bidirectional"))
    )
    (net (code "7") (name "/CANL") (class "Default")
      (node (ref "J1") (pin "2") (pinfunction "2_2") (pintype "passive"))
      (node (ref "J2") (pin "2") (pinfunction "2_2") (pintype "passive"))
      (node (ref "U7") (pin "6") (pinfunction "CANL_6") (pintype "bidirectional"))
      (node (ref "U7B") (pin "6") (pinfunction "CANL_6") (pintype "bidirectional"))
    )
    (net (code "8") (name "/GND4") (class "Default")
      (node (ref "U$1") (pin "GND4") (pinfunction "GND4_GND4") (pintype "power_in"))
    )
    (net (code "9") (name "/PWR_POS") (class "Default")
      (node (ref "J1") (pin "8") (pinfunction "8_8") (pintype "passive"))
      (node (ref "J2") (pin "8") (pinfunction "8_8") (pintype "passive"))
      (node (ref "R40") (pin "1") (pinfunction "1_1") (pintype "passive"))
    )
    (net (code "10") (name "/U5V") (class "Default")
      (node (ref "U$1") (pin "U5V") (pinfunction "U5V_U5V") (pintype "power_in"))
    )
    (net (code "11") (name "/VBAT") (class "Default")
      (node (ref "U$1") (pin "VBAT") (pinfunction "VBAT_VBAT") (pintype "power_in"))
    )
    (net (code "12") (name "/VDD") (class "Default")
      (node (ref "U$1") (pin "VDD") (pinfunction "VDD_VDD") (pintype "power_in"))
    )
    (net (code "13") (name "CANRX") (class "Default")
      (node (ref "U$1") (pin "PB8") (pinfunction "PB8_PB8") (pintype "bidirectional"))
      (node (ref "U7") (pin "4") (pinfunction "RXD_4") (pintype "output"))
      (node (ref "U7B") (pin "4") (pinfunction "RXD_4") (pintype "bidirectional"))
    )
    (net (code "14") (name "CANTX") (class "Default")
      (node (ref "U$1") (pin "PB9") (pinfunction "PB9_PB9") (pintype "bidirectional"))
      (node (ref "U7") (pin "1") (pinfunction "TXD_1") (pintype "input"))
      (node (ref "U7B") (pin "1") (pinfunction "TXD_1") (pintype "bidirectional"))
    )
    (net (code "15") (name "E_CS") (class "Default")
      (node (ref "JP2") (pin "4") (pinfunction "4_4") (pintype "passive"))
      (node (ref "R23") (pin "2") (pinfunction "2_2") (pintype "passive"))
      (node (ref "U$1") (pin "PC10") (pinfunction "PC10_PC10") (pintype "bidirectional"))
    )
    (net (code "16") (name "E_LAT") (class "Default")
      (node (ref "JP2") (pin "5") (pinfunction "5_5") (pintype "passive"))
      (node (ref "R22") (pin "2") (pinfunction "2_2") (pintype "passive"))
      (node (ref "U$1") (pin "PC11") (pinfunction "PC11_PC11") (pintype "bidirectional"))
    )
    (net (code "17") (name "GND") (class "Default")
      (node (ref "C1") (pin "2") (pinfunction "2_2") (pintype "passive"))
      (node (ref "C10") (pin "2") (pinfunction "2_2") (pintype "passive"))
      (node (ref "C11") (pin "2") (pinfunction "2_2") (pintype "passive"))
      (node (ref "C2") (pin "-") (pinfunction "-_-") (pintype "passive"))
      (node (ref "C3") (pin "2") (pinfunction "2_2") (pintype "passive"))
      (node (ref "C4") (pin "2") (pinfunction "2_2") (pintype "passive"))
      (node (ref "C5") (pin "2") (pinfunction "2_2") (pintype "passive"))
      (node (ref "C6") (pin "2") (pinfunction "2_2") (pintype "passive"))
      (node (ref "C7") (pin "2") (pinfunction "2_2") (pintype "passive"))
      (node (ref "C8") (pin "2") (pinfunction "2_2") (pintype "passive"))
      (node (ref "C9") (pin "2") (pinfunction "2_2") (pintype "passive"))
      (node (ref "D1") (pin "A") (pinfunction "A_A") (pintype "passive"))
      (node (ref "J1") (pin "3") (pinfunction "3_3") (pintype "passive"))
      (node (ref "J1") (pin "6") (pinfunction "6_6") (pintype "passive"))
      (node (ref "J1") (pin "7") (pinfunction "7_7") (pintype "passive"))
      (node (ref "J2") (pin "3") (pinfunction "3_3") (pintype "passive"))
      (node (ref "J2") (pin "6") (pinfunction "6_6") (pintype "passive"))
      (node (ref "J2") (pin "7") (pinfunction "7_7") (pintype "passive"))
      (node (ref "J3") (pin "2") (pinfunction "2_2") (pintype "passive"))
      (node (ref "J3") (pin "3") (pinfunction "3_3") (pintype "passive"))
      (node (ref "JP1") (pin "4") (pinfunction "4_4") (pintype "passive"))
      (node (ref "JP2") (pin "8") (pinfunction "8_8") (pintype "passive"))
      (node (ref "JP5") (pin "5") (pinfunction "5_5") (pintype "passive"))
      (node (ref "JP5") (pin "6") (pinfunction "6_6") (pintype "passive"))
      (node (ref "JP6") (pin "5") (pinfunction "5_5") (pintype "passive"))
      (node (ref "JP6") (pin "6") (pinfunction "6_6") (pintype "passive"))
      (node (ref "JP7") (pin "5") (pinfunction "5_5") (pintype "passive"))
      (node (ref "JP7") (pin "6") (pinfunction "6_6") (pintype "passive"))
      (node (ref "JP8") (pin "5") (pinfunction "5_5") (pintype "passive"))
      (node (ref "JP8") (pin "6") (pinfunction "6_6") (pintype "passive"))
      (node (ref "PORTA") (pin "5") (pinfunction "5_5") (pintype "passive"))
      (node (ref "PORTB") (pin "5") (pinfunction "5_5") (pintype "passive"))
      (node (ref "PORTC") (pin "5") (pinfunction "5_5") (pintype "passive"))
      (node (ref "Q1") (pin "2") (pinfunction "S_2") (pintype "passive"))
      (node (ref "Q10") (pin "2") (pinfunction "S_2") (pintype "passive"))
      (node (ref "Q11") (pin "2") (pinfunction "S_2") (pintype "passive"))
      (node (ref "Q12") (pin "2") (pinfunction "S_2") (pintype "passive"))
      (node (ref "Q13") (pin "2") (pinfunction "S_2") (pintype "passive"))
      (node (ref "Q14") (pin "2") (pinfunction "S_2") (pintype "passive"))
      (node (ref "Q15") (pin "2") (pinfunction "S_2") (pintype "passive"))
      (node (ref "Q16") (pin "2") (pinfunction "S_2") (pintype "passive"))
      (node (ref "Q2") (pin "2") (pinfunction "S_2") (pintype "passive"))
      (node (ref "Q3") (pin "2") (pinfunction "S_2") (pintype "passive"))
      (node (ref "Q4") (pin "2") (pinfunction "S_2") (pintype "passive"))
      (node (ref "Q5") (pin "2") (pinfunction "S_2") (pintype "passive"))
      (node (ref "Q6") (pin "2") (pinfunction "S_2") (pintype "passive"))
      (node (ref "Q7") (pin "2") (pinfunction "S_2") (pintype "passive"))
      (node (ref "Q8") (pin "2") (pinfunction "S_2") (pintype "passive"))
      (node (ref "Q9") (pin "2") (pinfunction "S_2") (pintype "passive"))
      (node (ref "R2") (pin "1") (pinfunction "1_1") (pintype "passive"))
      (node (ref "R61") (pin "2") (pinfunction "2_2") (pintype "passive"))
      (node (ref "SJ12") (pin "P$2") (pinfunction "2_P$2") (pintype "passive"))
      (node (ref "SJ3") (pin "2") (pinfunction "2_2") (pintype "passive"))
      (node (ref "SJ6") (pin "P$2") (pinfunction "2_P$2") (pintype "passive"))
      (node (ref "SJ9") (pin "2") (pinfunction "2_2") (pintype "passive"))
      (node (ref "U$1") (pin "GND3") (pinfunction "GND3_GND3") (pintype "power_in"))
      (node (ref "U$1") (pin "GND5") (pinfunction "GND5_GND5") (pintype "power_in"))
      (node (ref "U$1") (pin "GND6") (pinfunction "GND6_GND6") (pintype "power_in"))
      (node (ref "U$1") (pin "GND7") (pinfunction "GND7_GND7") (pintype "power_in"))
      (node (ref "U$1") (pin "GND8") (pinfunction "GND8_GND8") (pintype "power_in"))
      (node (ref "U1") (pin "6") (pinfunction "INH_6") (pintype "input"))
      (node (ref "U1") (pin "8") (pinfunction "GND_8") (pintype "power_in"))
      (node (ref "U10") (pin "11") (pinfunction "V-_11") (pintype "power_in"))
      (node (ref "U11") (pin "13") (pinfunction "G_13") (pintype "input"))
      (node (ref "U11") (pin "8") (pinfunction "GND_8") (pintype "power_in"))
      (node (ref "U13") (pin "13") (pinfunction "G_13") (pintype "input"))
      (node (ref "U13") (pin "8") (pinfunction "GND_8") (pintype "power_in"))
      (node (ref "U2") (pin "6") (pinfunction "INH_6") (pintype "input"))
      (node (ref "U2") (pin "8") (pinfunction "GND_8") (pintype "power_in"))
      (node (ref "U3") (pin "3") (pinfunction "VSS_3") (pintype "power_in"))
      (node (ref "U4") (pin "3") (pinfunction "VSS_3") (pintype "power_in"))
      (node (ref "U5") (pin "3") (pinfunction "VSS_3") (pintype "power_in"))
      (node (ref "U6") (pin "3") (pinfunction "VSS_3") (pintype "power_in"))
      (node (ref "U7") (pin "2") (pinfunction "GND_2") (pintype "power_in"))
      (node (ref "U7B") (pin "2") (pinfunction "VSS_2") (pintype "power_in"))
      (node (ref "U8") (pin "4") (pinfunction "SD_4") (pintype "bidirectional"))
      (node (ref "U8") (pin "5") (pinfunction "GND1_5") (pintype "power_in"))
      (node (ref "U8") (pin "6") (pinfunction "GND2_6") (pintype "power_in"))
      (node (ref "U8") (pin "7") (pinfunction "GND3_7") (pintype "power_in"))
      (node (ref "U8") (pin "8") (pinfunction "GND4_8") (pintype "power_in"))
      (node (ref "U8B") (pin "2") (pinfunction "GNDSIG_2") (pintype "input"))
      (node (ref "U8B") (pin "3") (pinfunction "~{ON/OFF}_3") (pintype "input"))
      (node (ref "U8B") (pin "4") (pinfunction "GND_4") (pintype "power_in"))
      (node (ref "U9") (pin "11") (pinfunction "V-_11") (pintype "power_in"))
      (node (ref "X6") (pin "2") (pinfunction "2_2") (pintype "passive"))
    )
    (net (code "18") (name "I2CSCL") (class "Default")
      (node (ref "JP1") (pin "2") (pinfunction "2_2") (pintype "passive"))
      (node (ref "R63") (pin "2") (pinfunction "2_2") (pintype "passive"))
      (node (ref "U$1") (pin "PB6") (pinfunction "PB6_PB6") (pintype "bidirectional"))
    )
    (net (code "19") (name "I2CSDA") (class "Default")
      (node (ref "JP1") (pin "1") (pinfunction "1_1") (pintype "passive"))
      (node (ref "R62") (pin "2") (pinfunction "2_2") (pintype "passive"))
      (node (ref "U$1") (pin "PB7") (pinfunction "PB7_PB7") (pintype "bidirectional"))
    )
    (net (code "20") (name "ILAT") (class "Default")
      (node (ref "U$1") (pin "PA6") (pinfunction "PA6_PA6") (pintype "bidirectional"))
      (node (ref "U1") (pin "15") (pinfunction "SH/~{LD}_15") (pintype "input"))
      (node (ref "U2") (pin "15") (pinfunction "SH/~{LD}_15") (pintype "input"))
    )
    (net (code "21") (name "MISO") (class "Default")
      (node (ref "JP2") (pin "1") (pinfunction "1_1") (pintype "passive"))
      (node (ref "U$1") (pin "PB4") (pinfunction "PB4_PB4") (pintype "bidirectional"))
    )
    (net (code "22") (name "MISO2") (class "Default")
      (node (ref "SJ13") (pin "P$2") (pinfunction "2_P$2") (pintype "passive"))
      (node (ref "U$1") (pin "PC2") (pinfunction "PC2_PC2") (pintype "bidirectional"))
      (node (ref "U2") (pin "13") (pinfunction "QH_13") (pintype "output"))
    )
    (net (code "23") (name "MOSI") (class "Default")
      (node (ref "R20") (pin "1") (pinfunction "1_1") (pintype "passive"))
      (node (ref "SJ15") (pin "1") (pinfunction "1_1") (pintype "passive"))
      (node (ref "SJ17") (pin "P$2") (pinfunction "2_P$2") (pintype "passive"))
      (node (ref "U$1") (pin "PB5") (pinfunction "PB5_PB5") (pintype "bidirectional"))
      (node (ref "U11") (pin "14") (pinfunction "SER_14") (pintype "input"))
    )
    (net (code "24") (name "Net-(D2-PadA)") (class "Default")
      (node (ref "D2") (pin "A") (pinfunction "A_A") (pintype "passive"))
      (node (ref "JP4") (pin "4") (pinfunction "4_4") (pintype "passive"))
    )
    (net (code "25") (name "Net-(D2-PadC)") (class "Default")
      (node (ref "D2") (pin "C") (pinfunction "C_C") (pintype "passive"))
      (node (ref "JP4") (pin "1") (pinfunction "1_1") (pintype "passive"))
    )
    (net (code "26") (name "Net-(J1-Pad4)") (class "Default")
      (node (ref "J1") (pin "4") (pinfunction "4_4") (pintype "passive"))
      (node (ref "J2") (pin "4") (pinfunction "4_4") (pintype "passive"))
    )
    (net (code "27") (name "Net-(J1-Pad5)") (class "Default")
      (node (ref "J1") (pin "5") (pinfunction "5_5") (pintype "passive"))
      (node (ref "J2") (pin "5") (pinfunction "5_5") (pintype "passive"))
    )
    (net (code "28") (name "Net-(JP4-Pad3)") (class "Default")
      (node (ref "JP4") (pin "3") (pinfunction "3_3") (pintype "passive"))
      (node (ref "R40") (pin "2") (pinfunction "2_2") (pintype "passive"))
    )
    (net (code "29") (name "Net-(PORTA-Pad1)") (class "Default")
      (node (ref "PORTA") (pin "1") (pinfunction "1_1") (pintype "passive"))
      (node (ref "R44") (pin "2") (pinfunction "2_2") (pintype "passive"))
      (node (ref "R53") (pin "2") (pinfunction "2_2") (pintype "passive"))
      (node (ref "RN3") (pin "1") (pinfunction "1_1") (pintype "passive"))
      (node (ref "RN4") (pin "9") (pinfunction "9_9") (pintype "passive"))
      (node (ref "X1") (pin "1") (pinfunction "1_1") (pintype "passive"))
    )
    (net (code "30") (name "Net-(PORTB-Pad1)") (class "Default")
      (node (ref "PORTB") (pin "1") (pinfunction "1_1") (pintype "passive"))
      (node (ref "R35") (pin "2") (pinfunction "2_2") (pintype "passive"))
      (node (ref "R45") (pin "2") (pinfunction "2_2") (pintype "passive"))
      (node (ref "RN1") (pin "1") (pinfunction "1_1") (pintype "passive"))
      (node (ref "RN2") (pin "9") (pinfunction "9_9") (pintype "passive"))
      (node (ref "X2") (pin "1") (pinfunction "1_1") (pintype "passive"))
    )
    (net (code "31") (name "Net-(Q1-D)") (class "Default")
      (node (ref "Q1") (pin "3") (pinfunction "D_3") (pintype "passive"))
      (node (ref "U12") (pin "18") (pinfunction "O1_18") (pintype "open_collector"))
      (node (ref "X5") (pin "1") (pinfunction "1_1") (pintype "passive"))
    )
    (net (code "32") (name "Net-(Q1-G)") (class "Default")
      (node (ref "Q1") (pin "1") (pinfunction "G_1") (pintype "passive"))
      (node (ref "R3") (pin "2") (pinfunction "2_2") (pintype "passive"))
    )
    (net (code "33") (name "Net-(Q2-D)") (class "Default")
      (node (ref "Q2") (pin "3") (pinfunction "D_3") (pintype "passive"))
      (node (ref "U12") (pin "17") (pinfunction "O2_17") (pintype "open_collector"))
      (node (ref "X5") (pin "2") (pinfunction "2_2") (pintype "passive"))
    )
    (net (code "34") (name "Net-(Q2-G)") (class "Default")
      (node (ref "Q2") (pin "1") (pinfunction "G_1") (pintype "passive"))
      (node (ref "R4") (pin "2") (pinfunction "2_2") (pintype "passive"))
    )
    (net (code "35") (name "Net-(Q3-D)") (class "Default")
      (node (ref "Q3") (pin "3") (pinfunction "D_3") (pintype "passive"))
      (node (ref "U12") (pin "16") (pinfunction "O3_16") (pintype "open_collector"))
      (node (ref "X5") (pin "3") (pinfunction "3_3") (pintype "passive"))
    )
    (net (code "36") (name "Net-(Q3-G)") (class "Default")
      (node (ref "Q3") (pin "1") (pinfunction "G_1") (pintype "passive"))
      (node (ref "R5") (pin "2") (pinfunction "2_2") (pintype "passive"))
    )
    (net (code "37") (name "Net-(Q4-D)") (class "Default")
      (node (ref "Q4") (pin "3") (pinfunction "D_3") (pintype "passive"))
      (node (ref "U12") (pin "15") (pinfunction "O4_15") (pintype "open_collector"))
      (node (ref "X5") (pin "4") (pinfunction "4_4") (pintype "passive"))
    )
    (net (code "38") (name "Net-(Q4-G)") (class "Default")
      (node (ref "Q4") (pin "1") (pinfunction "G_1") (pintype "passive"))
      (node (ref "R6") (pin "2") (pinfunction "2_2") (pintype "passive"))
    )
    (net (code "39") (name "Net-(Q5-D)") (class "Default")
      (node (ref "Q5") (pin "3") (pinfunction "D_3") (pintype "passive"))
      (node (ref "U12") (pin "14") (pinfunction "O5_14") (pintype "open_collector"))
      (node (ref "X5") (pin "5") (pinfunction "5_5") (pintype "passive"))
    )
    (net (code "40") (name "Net-(Q5-G)") (class "Default")
      (node (ref "Q5") (pin "1") (pinfunction "G_1") (pintype "passive"))
      (node (ref "R7") (pin "2") (pinfunction "2_2") (pintype "passive"))
    )
    (net (code "41") (name "Net-(Q6-D)") (class "Default")
      (node (ref "Q6") (pin "3") (pinfunction "D_3") (pintype "passive"))
      (node (ref "U12") (pin "13") (pinfunction "O6_13") (pintype "open_collector"))
      (node (ref "X5") (pin "6") (pinfunction "6_6") (pintype "passive"))
    )
    (net (code "42") (name "Net-(Q6-G)") (class "Default")
      (node (ref "Q6") (pin "1") (pinfunction "G_1") (pintype "passive"))
      (node (ref "R8") (pin "2") (pinfunction "2_2") (pintype "passive"))
    )
    (net (code "43") (name "Net-(Q7-D)") (class "Default")
      (node (ref "Q7") (pin "3") (pinfunction "D_3") (pintype "passive"))
      (node (ref "U12") (pin "12") (pinfunction "O7_12") (pintype "open_collector"))
      (node (ref "X5") (pin "7") (pinfunction "7_7") (pintype "passive"))
    )
    (net (code "44") (name "Net-(Q7-G)") (class "Default")
      (node (ref "Q7") (pin "1") (pinfunction "G_1") (pintype "passive"))
      (node (ref "R9") (pin "2") (pinfunction "2_2") (pintype "passive"))
    )
    (net (code "45") (name "Net-(Q8-D)") (class "Default")
      (node (ref "Q8") (pin "3") (pinfunction "D_3") (pintype "passive"))
      (node (ref "U12") (pin "11") (pinfunction "O8_11") (pintype "open_collector"))
      (node (ref "X5") (pin "8") (pinfunction "8_8") (pintype "passive"))
    )
    (net (code "46") (name "Net-(Q8-G)") (class "Default")
      (node (ref "Q8") (pin "1") (pinfunction "G_1") (pintype "passive"))
      (node (ref "R10") (pin "2") (pinfunction "2_2") (pintype "passive"))
    )
    (net (code "47") (name "Net-(Q9-D)") (class "Default")
      (node (ref "Q9") (pin "3") (pinfunction "D_3") (pintype "passive"))
      (node (ref "U14") (pin "18") (pinfunction "O1_18") (pintype "open_collector"))
      (node (ref "X4") (pin "1") (pinfunction "1_1") (pintype "passive"))
    )
    (net (code "48") (name "Net-(Q9-G)") (class "Default")
      (node (ref "Q9") (pin "1") (pinfunction "G_1") (pintype "passive"))
      (node (ref "R11") (pin "2") (pinfunction "2_2") (pintype "passive"))
    )
    (net (code "49") (name "Net-(Q10-D)") (class "Default")
      (node (ref "Q10") (pin "3") (pinfunction "D_3") (pintype "passive"))
      (node (ref "U14") (pin "17") (pinfunction "O2_17") (pintype "open_collector"))
      (node (ref "X4") (pin "2") (pinfunction "2_2") (pintype "passive"))
    )
    (net (code "50") (name "Net-(Q10-G)") (class "Default")
      (node (ref "Q10") (pin "1") (pinfunction "G_1") (pintype "passive"))
      (node (ref "R12") (pin "2") (pinfunction "2_2") (pintype "passive"))
    )
    (net (code "51") (name "Net-(Q11-D)") (class "Default")
      (node (ref "Q11") (pin "3") (pinfunction "D_3") (pintype "passive"))
      (node (ref "U14") (pin "16") (pinfunction "O3_16") (pintype "open_collector"))
      (node (ref "X4") (pin "3") (pinfunction "3_3") (pintype "passive"))
    )
    (net (code "52") (name "Net-(Q11-G)") (class "Default")
      (node (ref "Q11") (pin "1") (pinfunction "G_1") (pintype "passive"))
      (node (ref "R13") (pin "2") (pinfunction "2_2") (pintype "passive"))
    )
    (net (code "53") (name "Net-(Q12-D)") (class "Default")
      (node (ref "Q12") (pin "3") (pinfunction "D_3") (pintype "passive"))
      (node (ref "U14") (pin "15") (pinfunction "O4_15") (pintype "open_collector"))
      (node (ref "X4") (pin "4") (pinfunction "4_4") (pintype "passive"))
    )
    (net (code "54") (name "Net-(Q12-G)") (class "Default")
      (node (ref "Q12") (pin "1") (pinfunction "G_1") (pintype "passive"))
      (node (ref "R14") (pin "2") (pinfunction "2_2") (pintype "passive"))
    )
    (net (code "55") (name "Net-(Q13-D)") (class "Default")
      (node (ref "Q13") (pin "3") (pinfunction "D_3") (pintype "passive"))
      (node (ref "U14") (pin "14") (pinfunction "O5_14") (pintype "open_collector"))
      (node (ref "X4") (pin "5") (pinfunction "5_5") (pintype "passive"))
    )
    (net (code "56") (name "Net-(Q13-G)") (class "Default")
      (node (ref "Q13") (pin "1") (pinfunction "G_1") (pintype "passive"))
      (node (ref "R15") (pin "2") (pinfunction "2_2") (pintype "passive"))
    )
    (net (code "57") (name "Net-(Q14-D)") (class "Default")
      (node (ref "Q14") (pin "3") (pinfunction "D_3") (pintype "passive"))
      (node (ref "U14") (pin "13") (pinfunction "O6_13") (pintype "open_collector"))
      (node (ref "X4") (pin "6") (pinfunction "6_6") (pintype "passive"))
    )
    (net (code "58") (name "Net-(Q14-G)") (class "Default")
      (node (ref "Q14") (pin "1") (pinfunction "G_1") (pintype "passive"))
      (node (ref "R16") (pin "2") (pinfunction "2_2") (pintype "passive"))
    )
    (net (code "59") (name "Net-(Q15-D)") (class "Default")
      (node (ref "Q15") (pin "3") (pinfunction "D_3") (pintype "passive"))
      (node (ref "U14") (pin "12") (pinfunction "O7_12") (pintype "open_collector"))
      (node (ref "X4") (pin "7") (pinfunction "7_7") (pintype "passive"))
    )
    (net (code "60") (name "Net-(Q15-G)") (class "Default")
      (node (ref "Q15") (pin "1") (pinfunction "G_1") (pintype "passive"))
      (node (ref "R17") (pin "2") (pinfunction "2_2") (pintype "passive"))
    )
    (net (code "61") (name "Net-(Q16-D)") (class "Default")
      (node (ref "Q16") (pin "3") (pinfunction "D_3") (pintype "passive"))
      (node (ref "U14") (pin "11") (pinfunction "O8_11") (pintype "open_collector"))
      (node (ref "X4") (pin "8") (pinfunction "8_8") (pintype "passive"))
    )
    (net (code "62") (name "Net-(Q16-G)") (class "Default")
      (node (ref "Q16") (pin "1") (pinfunction "G_1") (pintype "passive"))
      (node (ref "R18") (pin "2") (pinfunction "2_2") (pintype "passive"))
    )
    (net (code "63") (name "Net-(RN1A-2)") (class "Default")
      (node (ref "R35") (pin "1") (pinfunction "1_1") (pintype "passive"))
      (node (ref "RN1") (pin "16") (pinfunction "2_16") (pintype "passive"))
      (node (ref "U2") (pin "14") (pinfunction "H_14") (pintype "input"))
    )
    (net (code "64") (name "Net-(RN1B-1)") (class "Default")
      (node (ref "PORTB") (pin "2") (pinfunction "2_2") (pintype "passive"))
      (node (ref "R34") (pin "2") (pinfunction "2_2") (pintype "passive"))
      (node (ref "R46") (pin "1") (pinfunction "1_1") (pintype "passive"))
      (node (ref "RN1") (pin "2") (pinfunction "1_2") (pintype "passive"))
      (node (ref "RN2") (pin "8") (pinfunction "8_8") (pintype "passive"))
      (node (ref "X2") (pin "2") (pinfunction "2_2") (pintype "passive"))
    )
    (net (code "65") (name "Net-(RN1B-2)") (class "Default")
      (node (ref "R34") (pin "1") (pinfunction "1_1") (pintype "passive"))
      (node (ref "RN1") (pin "15") (pinfunction "2_15") (pintype "passive"))
      (node (ref "U2") (pin "12") (pinfunction "G_12") (pintype "input"))
    )
    (net (code "66") (name "Net-(RN1C-1)") (class "Default")
      (node (ref "PORTB") (pin "3") (pinfunction "3_3") (pintype "passive"))
      (node (ref "R33") (pin "2") (pinfunction "2_2") (pintype "passive"))
      (node (ref "R47") (pin "1") (pinfunction "1_1") (pintype "passive"))
      (node (ref "RN1") (pin "3") (pinfunction "1_3") (pintype "passive"))
      (node (ref "RN2") (pin "7") (pinfunction "7_7") (pintype "passive"))
      (node (ref "X2") (pin "3") (pinfunction "3_3") (pintype "passive"))
    )
    (net (code "67") (name "Net-(RN1C-2)") (class "Default")
      (node (ref "R33") (pin "1") (pinfunction "1_1") (pintype "passive"))
      (node (ref "RN1") (pin "14") (pinfunction "2_14") (pintype "passive"))
      (node (ref "U2") (pin "11") (pinfunction "F_11") (pintype "input"))
    )
    (net (code "68") (name "Net-(RN1D-1)") (class "Default")
      (node (ref "PORTB") (pin "4") (pinfunction "4_4") (pintype "passive"))
      (node (ref "R32") (pin "2") (pinfunction "2_2") (pintype "passive"))
      (node (ref "R48") (pin "1") (pinfunction "1_1") (pintype "passive"))
      (node (ref "RN1") (pin "4") (pinfunction "1_4") (pintype "passive"))
      (node (ref "RN2") (pin "6") (pinfunction "6_6") (pintype "passive"))
      (node (ref "X2") (pin "4") (pinfunction "4_4") (pintype "passive"))
    )
    (net (code "69") (name "Net-(RN1D-2)") (class "Default")
      (node (ref "R32") (pin "1") (pinfunction "1_1") (pintype "passive"))
      (node (ref "RN1") (pin "13") (pinfunction "2_13") (pintype "passive"))
      (node (ref "U2") (pin "10") (pinfunction "E_10") (pintype "input"))
    )
    (net (code "70") (name "Net-(RN1E-1)") (class "Default")
      (node (ref "PORTB") (pin "7") (pinfunction "7_7") (pintype "passive"))
      (node (ref "R31") (pin "2") (pinfunction "2_2") (pintype "passive"))
      (node (ref "R49") (pin "1") (pinfunction "1_1") (pintype "passive"))
      (node (ref "RN1") (pin "5") (pinfunction "1_5") (pintype "passive"))
      (node (ref "RN2") (pin "5") (pinfunction "5_5") (pintype "passive"))
      (node (ref "X2") (pin "5") (pinfunction "5_5") (pintype "passive"))
    )
    (net (code "71") (name "Net-(RN1E-2)") (class "Default")
      (node (ref "R31") (pin "1") (pinfunction "1_1") (pintype "passive"))
      (node (ref "RN1") (pin "12") (pinfunction "2_12") (pintype "passive"))
      (node (ref "U2") (pin "5") (pinfunction "D_5") (pintype "input"))
    )
    (net (code "72") (name "Net-(RN1F-1)") (class "Default")
      (node (ref "PORTB") (pin "8") (pinfunction "8_8") (pintype "passive"))
      (node (ref "R30") (pin "2") (pinfunction "2_2") (pintype "passive"))
      (node (ref "R50") (pin "1") (pinfunction "1_1") (pintype "passive"))
      (node (ref "RN1") (pin "6") (pinfunction "1_6") (pintype "passive"))
      (node (ref "RN2") (pin "4") (pinfunction "4_4") (pintype "passive"))
      (node (ref "X2") (pin "6") (pinfunction "6_6") (pintype "passive"))
    )
    (net (code "73") (name "Net-(RN1F-2)") (class "Default")
      (node (ref "R30") (pin "1") (pinfunction "1_1") (pintype "passive"))
      (node (ref "RN1") (pin "11") (pinfunction "2_11") (pintype "passive"))
      (node (ref "U2") (pin "4") (pinfunction "C_4") (pintype "input"))
    )
    (net (code "74") (name "Net-(RN1G-1)") (class "Default")
      (node (ref "PORTB") (pin "9") (pinfunction "9_9") (pintype "passive"))
      (node (ref "R29") (pin "2") (pinfunction "2_2") (pintype "passive"))
      (node (ref "R51") (pin "1") (pinfunction "1_1") (pintype "passive"))
      (node (ref "RN1") (pin "7") (pinfunction "1_7") (pintype "passive"))
      (node (ref "RN2") (pin "3") (pinfunction "3_3") (pintype "passive"))
      (node (ref "X2") (pin "7") (pinfunction "7_7") (pintype "passive"))
    )
    (net (code "75") (name "Net-(RN1G-2)") (class "Default")
      (node (ref "R29") (pin "1") (pinfunction "1_1") (pintype "passive"))
      (node (ref "RN1") (pin "10") (pinfunction "2_10") (pintype "passive"))
      (node (ref "U2") (pin "3") (pinfunction "B_3") (pintype "input"))
    )
    (net (code "76") (name "Net-(RN1H-1)") (class "Default")
      (node (ref "PORTB") (pin "10") (pinfunction "10_10") (pintype "passive"))
      (node (ref "R28") (pin "2") (pinfunction "2_2") (pintype "passive"))
      (node (ref "R52") (pin "1") (pinfunction "1_1") (pintype "passive"))
      (node (ref "RN1") (pin "8") (pinfunction "1_8") (pintype "passive"))
      (node (ref "RN2") (pin "2") (pinfunction "2_2") (pintype "passive"))
      (node (ref "X2") (pin "8") (pinfunction "8_8") (pintype "passive"))
    )
    (net (code "77") (name "Net-(RN1H-2)") (class "Default")
      (node (ref "R28") (pin "1") (pinfunction "1_1") (pintype "passive"))
      (node (ref "RN1") (pin "9") (pinfunction "2_9") (pintype "passive"))
      (node (ref "U2") (pin "2") (pinfunction "A_2") (pintype "input"))
    )
    (net (code "78") (name "Net-(RN3A-2)") (class "Default")
      (node (ref "R44") (pin "1") (pinfunction "1_1") (pintype "passive"))
      (node (ref "RN3") (pin "16") (pinfunction "2_16") (pintype "passive"))
      (node (ref "U1") (pin "14") (pinfunction "H_14") (pintype "input"))
    )
    (net (code "79") (name "Net-(RN3B-1)") (class "Default")
      (node (ref "PORTA") (pin "2") (pinfunction "2_2") (pintype "passive"))
      (node (ref "R43") (pin "2") (pinfunction "2_2") (pintype "passive"))
      (node (ref "R54") (pin "2") (pinfunction "2_2") (pintype "passive"))
      (node (ref "RN3") (pin "2") (pinfunction "1_2") (pintype "passive"))
      (node (ref "RN4") (pin "8") (pinfunction "8_8") (pintype "passive"))
      (node (ref "X1") (pin "2") (pinfunction "2_2") (pintype "passive"))
    )
    (net (code "80") (name "Net-(RN3B-2)") (class "Default")
      (node (ref "R43") (pin "1") (pinfunction "1_1") (pintype "passive"))
      (node (ref "RN3") (pin "15") (pinfunction "2_15") (pintype "passive"))
      (node (ref "U1") (pin "12") (pinfunction "G_12") (pintype "input"))
    )
    (net (code "81") (name "Net-(RN3C-1)") (class "Default")
      (node (ref "PORTA") (pin "3") (pinfunction "3_3") (pintype "passive"))
      (node (ref "R42") (pin "2") (pinfunction "2_2") (pintype "passive"))
      (node (ref "R55") (pin "2") (pinfunction "2_2") (pintype "passive"))
      (node (ref "RN3") (pin "3") (pinfunction "1_3") (pintype "passive"))
      (node (ref "RN4") (pin "7") (pinfunction "7_7") (pintype "passive"))
      (node (ref "X1") (pin "3") (pinfunction "3_3") (pintype "passive"))
    )
    (net (code "82") (name "Net-(RN3C-2)") (class "Default")
      (node (ref "R42") (pin "1") (pinfunction "1_1") (pintype "passive"))
      (node (ref "RN3") (pin "14") (pinfunction "2_14") (pintype "passive"))
      (node (ref "U1") (pin "11") (pinfunction "F_11") (pintype "input"))
    )
    (net (code "83") (name "Net-(RN3D-1)") (class "Default")
      (node (ref "PORTA") (pin "4") (pinfunction "4_4") (pintype "passive"))
      (node (ref "R41") (pin "2") (pinfunction "2_2") (pintype "passive"))
      (node (ref "R56") (pin "2") (pinfunction "2_2") (pintype "passive"))
      (node (ref "RN3") (pin "4") (pinfunction "1_4") (pintype "passive"))
      (node (ref "RN4") (pin "6") (pinfunction "6_6") (pintype "passive"))
      (node (ref "X1") (pin "4") (pinfunction "4_4") (pintype "passive"))
    )
    (net (code "84") (name "Net-(RN3D-2)") (class "Default")
      (node (ref "R41") (pin "1") (pinfunction "1_1") (pintype "passive"))
      (node (ref "RN3") (pin "13") (pinfunction "2_13") (pintype "passive"))
      (node (ref "U1") (pin "10") (pinfunction "E_10") (pintype "input"))
    )
    (net (code "85") (name "Net-(RN3E-1)") (class "Default")
      (node (ref "PORTA") (pin "7") (pinfunction "7_7") (pintype "passive"))
      (node (ref "R39") (pin "2") (pinfunction "2_2") (pintype "passive"))
      (node (ref "R57") (pin "2") (pinfunction "2_2") (pintype "passive"))
      (node (ref "RN3") (pin "5") (pinfunction "1_5") (pintype "passive"))
      (node (ref "RN4") (pin "5") (pinfunction "5_5") (pintype "passive"))
      (node (ref "X1") (pin "5") (pinfunction "5_5") (pintype "passive"))
    )
    (net (code "86") (name "Net-(RN3E-2)") (class "Default")
      (node (ref "R39") (pin "1") (pinfunction "1_1") (pintype "passive"))
      (node (ref "RN3") (pin "12") (pinfunction "2_12") (pintype "passive"))
      (node (ref "U1") (pin "5") (pinfunction "D_5") (pintype "input"))
    )
    (net (code "87") (name "Net-(RN3F-1)") (class "Default")
      (node (ref "PORTA") (pin "8") (pinfunction "8_8") (pintype "passive"))
      (node (ref "R38") (pin "2") (pinfunction "2_2") (pintype "passive"))
      (node (ref "R58") (pin "2") (pinfunction "2_2") (pintype "passive"))
      (node (ref "RN3") (pin "6") (pinfunction "1_6") (pintype "passive"))
      (node (ref "RN4") (pin "4") (pinfunction "4_4") (pintype "passive"))
      (node (ref "X1") (pin "6") (pinfunction "6_6") (pintype "passive"))
    )
    (net (code "88") (name "Net-(RN3F-2)") (class "Default")
      (node (ref "R38") (pin "1") (pinfunction "1_1") (pintype "passive"))
      (node (ref "RN3") (pin "11") (pinfunction "2_11") (pintype "passive"))
      (node (ref "U1") (pin "4") (pinfunction "C_4") (pintype "input"))
    )
    (net (code "89") (name "Net-(RN3G-1)") (class "Default")
      (node (ref "PORTA") (pin "9") (pinfunction "9_9") (pintype "passive"))
      (node (ref "R37") (pin "2") (pinfunction "2_2") (pintype "passive"))
      (node (ref "R59") (pin "2") (pinfunction "2_2") (pintype "passive"))
      (node (ref "RN3") (pin "7") (pinfunction "1_7") (pintype "passive"))
      (node (ref "RN4") (pin "3") (pinfunction "3_3") (pintype "passive"))
      (node (ref "X1") (pin "7") (pinfunction "7_7") (pintype "passive"))
    )
    (net (code "90") (name "Net-(RN3G-2)") (class "Default")
      (node (ref "R37") (pin "1") (pinfunction "1_1") (pintype "passive"))
      (node (ref "RN3") (pin "10") (pinfunction "2_10") (pintype "passive"))
      (node (ref "U1") (pin "3") (pinfunction "B_3") (pintype "input"))
    )
    (net (code "91") (name "Net-(RN3H-1)") (class "Default")
      (node (ref "PORTA") (pin "10") (pinfunction "10_10") (pintype "passive"))
      (node (ref "R36") (pin "2") (pinfunction "2_2") (pintype "passive"))
      (node (ref "R60") (pin "2") (pinfunction "2_2") (pintype "passive"))
      (node (ref "RN3") (pin "8") (pinfunction "1_8") (pintype "passive"))
      (node (ref "RN4") (pin "2") (pinfunction "2_2") (pintype "passive"))
      (node (ref "X1") (pin "8") (pinfunction "8_8") (pintype "passive"))
    )
    (net (code "92") (name "Net-(RN3H-2)") (class "Default")
      (node (ref "R36") (pin "1") (pinfunction "1_1") (pintype "passive"))
      (node (ref "RN3") (pin "9") (pinfunction "2_9") (pintype "passive"))
      (node (ref "U1") (pin "2") (pinfunction "A_2") (pintype "input"))
    )
    (net (code "93") (name "Net-(SJ1-1)") (class "Default")
      (node (ref "SJ1") (pin "P$1") (pinfunction "1_P$1") (pintype "passive"))
      (node (ref "SJ2") (pin "P$1") (pinfunction "1_P$1") (pintype "passive"))
      (node (ref "SJ3") (pin "1") (pinfunction "1_1") (pintype "passive"))
      (node (ref "U12") (pin "9") (pinfunction "GND_9") (pintype "power_in"))
    )
    (net (code "94") (name "Net-(SJ4-1)") (class "Default")
      (node (ref "SJ4") (pin "P$1") (pinfunction "1_P$1") (pintype "passive"))
      (node (ref "SJ5") (pin "P$1") (pinfunction "1_P$1") (pintype "passive"))
      (node (ref "SJ6") (pin "P$1") (pinfunction "1_P$1") (pintype "passive"))
      (node (ref "U12") (pin "10") (pinfunction "CD+_10") (pintype "passive"))
    )
    (net (code "95") (name "Net-(SJ7-1)") (class "Default")
      (node (ref "SJ7") (pin "P$1") (pinfunction "1_P$1") (pintype "passive"))
      (node (ref "SJ8") (pin "P$1") (pinfunction "1_P$1") (pintype "passive"))
      (node (ref "SJ9") (pin "1") (pinfunction "1_1") (pintype "passive"))
      (node (ref "U14") (pin "9") (pinfunction "GND_9") (pintype "power_in"))
    )
    (net (code "96") (name "Net-(SJ10-1)") (class "Default")
      (node (ref "SJ10") (pin "P$1") (pinfunction "1_P$1") (pintype "passive"))
      (node (ref "SJ11") (pin "P$1") (pinfunction "1_P$1") (pintype "passive"))
      (node (ref "SJ12") (pin "P$1") (pinfunction "1_P$1") (pintype "passive"))
      (node (ref "U14") (pin "10") (pinfunction "CD+_10") (pintype "passive"))
    )
    (net (code "97") (name "Net-(SJ13-1)") (class "Default")
      (node (ref "SJ13") (pin "P$1") (pinfunction "1_P$1") (pintype "passive"))
      (node (ref "U$1") (pin "PB14") (pinfunction "PB14_PB14") (pintype "bidirectional"))
    )
    (net (code "98") (name "Net-(SJ14-1)") (class "Default")
      (node (ref "SJ14") (pin "P$1") (pinfunction "1_P$1") (pintype "passive"))
      (node (ref "U$1") (pin "VIN2") (pinfunction "VIN2_VIN2") (pintype "power_in"))
    )
    (net (code "99") (name "Net-(SJ16-2)") (class "Default")
      (node (ref "JP2") (pin "2") (pinfunction "2_2") (pintype "passive"))
      (node (ref "SJ15") (pin "2") (pinfunction "2_2") (pintype "passive"))
      (node (ref "SJ16") (pin "P$2") (pinfunction "2_P$2") (pintype "passive"))
    )
    (net (code "100") (name "Net-(SJ18-2)") (class "Default")
      (node (ref "SJ18") (pin "P$2") (pinfunction "2_P$2") (pintype "passive"))
      (node (ref "U7") (pin "5") (pinfunction "VREF_5") (pintype "output"))
      (node (ref "U7B") (pin "5") (pinfunction "VREF_5") (pintype "bidirectional"))
    )
    (net (code "101") (name "Net-(U3A-O)") (class "Default")
      (node (ref "PORTC") (pin "1") (pinfunction "1_1") (pintype "passive"))
      (node (ref "U3") (pin "7") (pinfunction "O_7") (pintype "output"))
      (node (ref "U9") (pin "7") (pinfunction "OUT_7") (pintype "output"))
      (node (ref "X3") (pin "1") (pinfunction "1_1") (pintype "passive"))
    )
    (net (code "102") (name "Net-(U3B-O)") (class "Default")
      (node (ref "PORTC") (pin "2") (pinfunction "2_2") (pintype "passive"))
      (node (ref "U3") (pin "5") (pinfunction "O_5") (pintype "output"))
      (node (ref "U9") (pin "8") (pinfunction "OUT_8") (pintype "output"))
      (node (ref "X3") (pin "2") (pinfunction "2_2") (pintype "passive"))
    )
    (net (code "103") (name "Net-(U4A-O)") (class "Default")
      (node (ref "PORTC") (pin "4") (pinfunction "4_4") (pintype "passive"))
      (node (ref "U4") (pin "7") (pinfunction "O_7") (pintype "output"))
      (node (ref "U9") (pin "14") (pinfunction "OUT_14") (pintype "output"))
      (node (ref "X3") (pin "4") (pinfunction "4_4") (pintype "passive"))
    )
    (net (code "104") (name "Net-(U4B-O)") (class "Default")
      (node (ref "PORTC") (pin "3") (pinfunction "3_3") (pintype "passive"))
      (node (ref "U4") (pin "5") (pinfunction "O_5") (pintype "output"))
      (node (ref "U9") (pin "1") (pinfunction "OUT_1") (pintype "output"))
      (node (ref "X3") (pin "3") (pinfunction "3_3") (pintype "passive"))
    )
    (net (code "105") (name "Net-(U7-RS)") (class "Default")
      (node (ref "R61") (pin "1") (pinfunction "1_1") (pintype "passive"))
      (node (ref "U7") (pin "8") (pinfunction "RS_8") (pintype "input"))
      (node (ref "U7B") (pin "8") (pinfunction "RS_8") (pintype "bidirectional"))
    )
    (net (code "106") (name "Net-(U8-VOUT)") (class "Default")
      (node (ref "D1") (pin "C") (pinfunction "C_C") (pintype "passive"))
      (node (ref "L1") (pin "2") (pinfunction "2_2") (pintype "passive"))
      (node (ref "U8") (pin "2") (pinfunction "VOUT_2") (pintype "bidirectional"))
      (node (ref "U8B") (pin "7") (pinfunction "OUT_7") (pintype "passive"))
    )
    (net (code "107") (name "Net-(U10A--IN)") (class "Default")
      (node (ref "R1") (pin "1") (pinfunction "1_1") (pintype "passive"))
      (node (ref "R2") (pin "2") (pinfunction "2_2") (pintype "passive"))
      (node (ref "U10") (pin "13") (pinfunction "-IN_13") (pintype "input"))
      (node (ref "U10") (pin "2") (pinfunction "-IN_2") (pintype "input"))
      (node (ref "U10") (pin "6") (pinfunction "-IN_6") (pintype "input"))
      (node (ref "U10") (pin "9") (pinfunction "-IN_9") (pintype "input"))
      (node (ref "U9") (pin "13") (pinfunction "-IN_13") (pintype "input"))
      (node (ref "U9") (pin "2") (pinfunction "-IN_2") (pintype "input"))
      (node (ref "U9") (pin "6") (pinfunction "-IN_6") (pintype "input"))
      (node (ref "U9") (pin "9") (pinfunction "-IN_9") (pintype "input"))
    )
    (net (code "108") (name "Net-(U10A-OUT)") (class "Default")
      (node (ref "PORTC") (pin "9") (pinfunction "9_9") (pintype "passive"))
      (node (ref "U10") (pin "1") (pinfunction "OUT_1") (pintype "output"))
      (node (ref "U6") (pin "5") (pinfunction "O_5") (pintype "output"))
      (node (ref "X3") (pin "7") (pinfunction "7_7") (pintype "passive"))
    )
    (net (code "109") (name "Net-(U10B-OUT)") (class "Default")
      (node (ref "PORTC") (pin "7") (pinfunction "7_7") (pintype "passive"))
      (node (ref "U10") (pin "7") (pinfunction "OUT_7") (pintype "output"))
      (node (ref "U5") (pin "7") (pinfunction "O_7") (pintype "output"))
      (node (ref "X3") (pin "5") (pinfunction "5_5") (pintype "passive"))
    )
    (net (code "110") (name "Net-(U10C-OUT)") (class "Default")
      (node (ref "PORTC") (pin "8") (pinfunction "8_8") (pintype "passive"))
      (node (ref "U10") (pin "8") (pinfunction "OUT_8") (pintype "output"))
      (node (ref "U5") (pin "5") (pinfunction "O_5") (pintype "output"))
      (node (ref "X3") (pin "6") (pinfunction "6_6") (pintype "passive"))
    )
    (net (code "111") (name "Net-(U10D-OUT)") (class "Default")
      (node (ref "PORTC") (pin "10") (pinfunction "10_10") (pintype "passive"))
      (node (ref "U10") (pin "14") (pinfunction "OUT_14") (pintype "output"))
      (node (ref "U6") (pin "7") (pinfunction "O_7") (pintype "output"))
      (node (ref "X3") (pin "8") (pinfunction "8_8") (pintype "passive"))
    )
    (net (code "112") (name "Net-(U11A-QA)") (class "Default")
      (node (ref "R3") (pin "1") (pinfunction "1_1") (pintype "passive"))
      (node (ref "U11") (pin "15") (pinfunction "QA_15") (pintype "tri_state"))
      (node (ref "U12") (pin "1") (pinfunction "I1_1") (pintype "input"))
    )
    (net (code "113") (name "Net-(U11A-QB)") (class "Default")
      (node (ref "R4") (pin "1") (pinfunction "1_1") (pintype "passive"))
      (node (ref "U11") (pin "1") (pinfunction "QB_1") (pintype "tri_state"))
      (node (ref "U12") (pin "2") (pinfunction "I2_2") (pintype "input"))
    )
    (net (code "114") (name "Net-(U11A-QC)") (class "Default")
      (node (ref "R5") (pin "1") (pinfunction "1_1") (pintype "passive"))
      (node (ref "U11") (pin "2") (pinfunction "QC_2") (pintype "tri_state"))
      (node (ref "U12") (pin "3") (pinfunction "I3_3") (pintype "input"))
    )
    (net (code "115") (name "Net-(U11A-QD)") (class "Default")
      (node (ref "R6") (pin "1") (pinfunction "1_1") (pintype "passive"))
      (node (ref "U11") (pin "3") (pinfunction "QD_3") (pintype "tri_state"))
      (node (ref "U12") (pin "4") (pinfunction "I4_4") (pintype "input"))
    )
    (net (code "116") (name "Net-(U11A-QE)") (class "Default")
      (node (ref "R7") (pin "1") (pinfunction "1_1") (pintype "passive"))
      (node (ref "U11") (pin "4") (pinfunction "QE_4") (pintype "tri_state"))
      (node (ref "U12") (pin "5") (pinfunction "I5_5") (pintype "input"))
    )
    (net (code "117") (name "Net-(U11A-QF)") (class "Default")
      (node (ref "R8") (pin "1") (pinfunction "1_1") (pintype "passive"))
      (node (ref "U11") (pin "5") (pinfunction "QF_5") (pintype "tri_state"))
      (node (ref "U12") (pin "6") (pinfunction "I6_6") (pintype "input"))
    )
    (net (code "118") (name "Net-(U11A-QG)") (class "Default")
      (node (ref "R9") (pin "1") (pinfunction "1_1") (pintype "passive"))
      (node (ref "U11") (pin "6") (pinfunction "QG_6") (pintype "tri_state"))
      (node (ref "U12") (pin "7") (pinfunction "I7_7") (pintype "input"))
    )
    (net (code "119") (name "Net-(U11A-QH)") (class "Default")
      (node (ref "R10") (pin "1") (pinfunction "1_1") (pintype "passive"))
      (node (ref "U11") (pin "7") (pinfunction "QH_7") (pintype "tri_state"))
      (node (ref "U12") (pin "8") (pinfunction "I8_8") (pintype "input"))
    )
    (net (code "120") (name "Net-(U13A-QA)") (class "Default")
      (node (ref "R11") (pin "1") (pinfunction "1_1") (pintype "passive"))
      (node (ref "U13") (pin "15") (pinfunction "QA_15") (pintype "tri_state"))
      (node (ref "U14") (pin "1") (pinfunction "I1_1") (pintype "input"))
    )
    (net (code "121") (name "Net-(U13A-QB)") (class "Default")
      (node (ref "R12") (pin "1") (pinfunction "1_1") (pintype "passive"))
      (node (ref "U13") (pin "1") (pinfunction "QB_1") (pintype "tri_state"))
      (node (ref "U14") (pin "2") (pinfunction "I2_2") (pintype "input"))
    )
    (net (code "122") (name "Net-(U13A-QC)") (class "Default")
      (node (ref "R13") (pin "1") (pinfunction "1_1") (pintype "passive"))
      (node (ref "U13") (pin "2") (pinfunction "QC_2") (pintype "tri_state"))
      (node (ref "U14") (pin "3") (pinfunction "I3_3") (pintype "input"))
    )
    (net (code "123") (name "Net-(U13A-QD)") (class "Default")
      (node (ref "R14") (pin "1") (pinfunction "1_1") (pintype "passive"))
      (node (ref "U13") (pin "3") (pinfunction "QD_3") (pintype "tri_state"))
      (node (ref "U14") (pin "4") (pinfunction "I4_4") (pintype "input"))
    )
    (net (code "124") (name "Net-(U13A-QE)") (class "Default")
      (node (ref "R15") (pin "1") (pinfunction "1_1") (pintype "passive"))
      (node (ref "U13") (pin "4") (pinfunction "QE_4") (pintype "tri_state"))
      (node (ref "U14") (pin "5") (pinfunction "I5_5") (pintype "input"))
    )
    (net (code "125") (name "Net-(U13A-QF)") (class "Default")
      (node (ref "R16") (pin "1") (pinfunction "1_1") (pintype "passive"))
      (node (ref "U13") (pin "5") (pinfunction "QF_5") (pintype "tri_state"))
      (node (ref "U14") (pin "6") (pinfunction "I6_6") (pintype "input"))
    )
    (net (code "126") (name "Net-(U13A-QG)") (class "Default")
      (node (ref "R17") (pin "1") (pinfunction "1_1") (pintype "passive"))
      (node (ref "U13") (pin "6") (pinfunction "QG_6") (pintype "tri_state"))
      (node (ref "U14") (pin "7") (pinfunction "I7_7") (pintype "input"))
    )
    (net (code "127") (name "Net-(U13A-QH)") (class "Default")
      (node (ref "R18") (pin "1") (pinfunction "1_1") (pintype "passive"))
      (node (ref "U13") (pin "7") (pinfunction "QH_7") (pintype "tri_state"))
      (node (ref "U14") (pin "8") (pinfunction "I8_8") (pintype "input"))
    )
    (net (code "128") (name "OLAT") (class "Default")
      (node (ref "R21") (pin "1") (pinfunction "1_1") (pintype "passive"))
      (node (ref "U$1") (pin "PA8") (pinfunction "PA8_PA8") (pintype "bidirectional"))
      (node (ref "U11") (pin "12") (pinfunction "RCK_12") (pintype "input"))
      (node (ref "U13") (pin "12") (pinfunction "RCK_12") (pintype "input"))
    )
    (net (code "129") (name "SCK") (class "Default")
      (node (ref "JP2") (pin "3") (pinfunction "3_3") (pintype "passive"))
      (node (ref "R19") (pin "1") (pinfunction "1_1") (pintype "passive"))
      (node (ref "U$1") (pin "PB3") (pinfunction "PB3_PB3") (pintype "bidirectional"))
      (node (ref "U11") (pin "11") (pinfunction "SCK_11") (pintype "input"))
      (node (ref "U13") (pin "11") (pinfunction "SCK_11") (pintype "input"))
    )
    (net (code "130") (name "SCK2") (class "Default")
      (node (ref "U$1") (pin "PB10") (pinfunction "PB10_PB10") (pintype "bidirectional"))
      (node (ref "U1") (pin "7") (pinfunction "CLK_7") (pintype "input"))
      (node (ref "U2") (pin "7") (pinfunction "CLK_7") (pintype "input"))
    )
    (net (code "131") (name "SLNK1") (class "Default")
      (node (ref "SJ17") (pin "P$1") (pinfunction "1_P$1") (pintype "passive"))
      (node (ref "U11") (pin "9") (pinfunction "QH*_9") (pintype "tri_state"))
      (node (ref "U13") (pin "14") (pinfunction "SER_14") (pintype "input"))
    )
    (net (code "132") (name "SLNK2") (class "Default")
      (node (ref "SJ16") (pin "P$1") (pinfunction "1_P$1") (pintype "passive"))
      (node (ref "U13") (pin "9") (pinfunction "QH*_9") (pintype "tri_state"))
    )
    (net (code "133") (name "SLNK3") (class "Default")
      (node (ref "U1") (pin "13") (pinfunction "QH_13") (pintype "output"))
      (node (ref "U2") (pin "1") (pinfunction "SER_1") (pintype "input"))
    )
    (net (code "134") (name "SRV1") (class "Default")
      (node (ref "JP5") (pin "2") (pinfunction "2_2") (pintype "passive"))
      (node (ref "R24") (pin "2") (pinfunction "2_2") (pintype "passive"))
      (node (ref "U$1") (pin "PC9") (pinfunction "PC9_PC9") (pintype "bidirectional"))
    )
    (net (code "135") (name "SRV2") (class "Default")
      (node (ref "JP5") (pin "1") (pinfunction "1_1") (pintype "passive"))
      (node (ref "R25") (pin "2") (pinfunction "2_2") (pintype "passive"))
      (node (ref "U$1") (pin "PC7") (pinfunction "PC7_PC7") (pintype "bidirectional"))
    )
    (net (code "136") (name "SRV3") (class "Default")
      (node (ref "JP6") (pin "2") (pinfunction "2_2") (pintype "passive"))
      (node (ref "R26") (pin "2") (pinfunction "2_2") (pintype "passive"))
      (node (ref "U$1") (pin "PC8") (pinfunction "PC8_PC8") (pintype "bidirectional"))
    )
    (net (code "137") (name "SRV4") (class "Default")
      (node (ref "JP6") (pin "1") (pinfunction "1_1") (pintype "passive"))
      (node (ref "R27") (pin "2") (pinfunction "2_2") (pintype "passive"))
      (node (ref "U$1") (pin "PC6") (pinfunction "PC6_PC6") (pintype "bidirectional"))
    )
    (net (code "138") (name "SRV5") (class "Default")
      (node (ref "JP7") (pin "2") (pinfunction "2_2") (pintype "passive"))
      (node (ref "R64") (pin "2") (pinfunction "2_2") (pintype "passive"))
      (node (ref "U$1") (pin "PF1-PH1") (pinfunction "PF1-PH1_PF1-PH1") (pintype "bidirectional"))
    )
    (net (code "139") (name "SRV6") (class "Default")
      (node (ref "JP7") (pin "1") (pinfunction "1_1") (pintype "passive"))
      (node (ref "R65") (pin "2") (pinfunction "2_2") (pintype "passive"))
      (node (ref "U$1") (pin "PA15") (pinfunction "PA15_PA15") (pintype "bidirectional"))
    )
    (net (code "140") (name "SRV7") (class "Default")
      (node (ref "JP8") (pin "2") (pinfunction "2_2") (pintype "passive"))
      (node (ref "R66") (pin "2") (pinfunction "2_2") (pintype "passive"))
      (node (ref "U$1") (pin "PC12") (pinfunction "PC12_PC12") (pintype "bidirectional"))
    )
    (net (code "141") (name "SRV8") (class "Default")
      (node (ref "JP8") (pin "1") (pinfunction "1_1") (pintype "passive"))
      (node (ref "R67") (pin "2") (pinfunction "2_2") (pintype "passive"))
      (node (ref "U$1") (pin "PD2") (pinfunction "PD2_PD2") (pintype "bidirectional"))
    )
    (net (code "142") (name "TDRV1") (class "Default")
      (node (ref "U$1") (pin "PB12") (pinfunction "PB12_PB12") (pintype "bidirectional"))
      (node (ref "U10") (pin "12") (pinfunction "+IN_12") (pintype "input"))
      (node (ref "U6") (pin "2") (pinfunction "I_2") (pintype "input"))
    )
    (net (code "143") (name "TDRV2") (class "Default")
      (node (ref "U$1") (pin "PB2") (pinfunction "PB2_PB2") (pintype "bidirectional"))
      (node (ref "U10") (pin "3") (pinfunction "+IN_3") (pintype "input"))
      (node (ref "U6") (pin "4") (pinfunction "I_4") (pintype "input"))
    )
    (net (code "144") (name "TDRV3") (class "Default")
      (node (ref "U$1") (pin "PB15") (pinfunction "PB15_PB15") (pintype "bidirectional"))
      (node (ref "U10") (pin "10") (pinfunction "+IN_10") (pintype "input"))
      (node (ref "U5") (pin "4") (pinfunction "I_4") (pintype "input"))
    )
    (net (code "145") (name "TDRV4") (class "Default")
      (node (ref "U$1") (pin "PB1") (pinfunction "PB1_PB1") (pintype "bidirectional"))
      (node (ref "U10") (pin "5") (pinfunction "+IN_5") (pintype "input"))
      (node (ref "U5") (pin "2") (pinfunction "I_2") (pintype "input"))
    )
    (net (code "146") (name "TDRV5") (class "Default")
      (node (ref "U$1") (pin "PA0") (pinfunction "PA0_PA0") (pintype "bidirectional"))
      (node (ref "U4") (pin "2") (pinfunction "I_2") (pintype "input"))
      (node (ref "U9") (pin "12") (pinfunction "+IN_12") (pintype "input"))
    )
    (net (code "147") (name "TDRV6") (class "Default")
      (node (ref "U$1") (pin "PA4") (pinfunction "PA4_PA4") (pintype "bidirectional"))
      (node (ref "U4") (pin "4") (pinfunction "I_4") (pintype "input"))
      (node (ref "U9") (pin "3") (pinfunction "+IN_3") (pintype "input"))
    )
    (net (code "148") (name "TDRV7") (class "Default")
      (node (ref "U$1") (pin "PC3") (pinfunction "PC3_PC3") (pintype "bidirectional"))
      (node (ref "U3") (pin "4") (pinfunction "I_4") (pintype "input"))
      (node (ref "U9") (pin "10") (pinfunction "+IN_10") (pintype "input"))
    )
    (net (code "149") (name "TDRV8") (class "Default")
      (node (ref "U$1") (pin "PC0") (pinfunction "PC0_PC0") (pintype "bidirectional"))
      (node (ref "U3") (pin "2") (pinfunction "I_2") (pintype "input"))
      (node (ref "U9") (pin "5") (pinfunction "+IN_5") (pintype "input"))
    )
    (net (code "150") (name "V+") (class "Default")
      (node (ref "C1") (pin "1") (pinfunction "1_1") (pintype "passive"))
      (node (ref "C2") (pin "+") (pinfunction "+_+") (pintype "passive"))
      (node (ref "L1") (pin "1") (pinfunction "1_1") (pintype "passive"))
      (node (ref "U$1") (pin "E5V") (pinfunction "E5V_E5V") (pintype "power_in"))
      (node (ref "U8") (pin "3") (pinfunction "FB_3") (pintype "bidirectional"))
      (node (ref "U8B") (pin "1") (pinfunction "FB_1") (pintype "input"))
    )
    (net (code "151") (name "unconnected-(H1-MOUNT-PadB3,3)") (class "Default")
      (node (ref "H1") (pin "B3,3") (pinfunction "MOUNT_B3,3") (pintype "passive"))
    )
    (net (code "152") (name "unconnected-(H2-MOUNT-PadB3,3)") (class "Default")
      (node (ref "H2") (pin "B3,3") (pinfunction "MOUNT_B3,3") (pintype "passive"))
    )
    (net (code "153") (name "unconnected-(H3-MOUNT-PadB3,3)") (class "Default")
      (node (ref "H3") (pin "B3,3") (pinfunction "MOUNT_B3,3") (pintype "passive"))
    )
    (net (code "154") (name "unconnected-(H4-MOUNT-PadB3,3)") (class "Default")
      (node (ref "H4") (pin "B3,3") (pinfunction "MOUNT_B3,3") (pintype "passive"))
    )
    (net (code "155") (name "unconnected-(U$1-PadBOOT0)") (class "Default")
      (node (ref "U$1") (pin "BOOT0") (pinfunction "BOOT0_BOOT0") (pintype "bidirectional"))
    )
    (net (code "156") (name "unconnected-(U$1-PadIOREF2)") (class "Default")
      (node (ref "U$1") (pin "IOREF2") (pinfunction "IOREF2_IOREF2") (pintype "input"))
    )
    (net (code "157") (name "unconnected-(U$1-PadNC1-PF7)") (class "Default")
      (node (ref "U$1") (pin "NC1-PF7") (pinfunction "NC1-PF7_NC1-PF7") (pintype "bidirectional"))
    )
    (net (code "158") (name "unconnected-(U$1-PadNC2-PF6)") (class "Default")
      (node (ref "U$1") (pin "NC2-PF6") (pinfunction "NC2-PF6_NC2-PF6") (pintype "bidirectional"))
    )
    (net (code "159") (name "unconnected-(U$1-PadNC3)") (class "Default")
      (node (ref "U$1") (pin "NC3") (pinfunction "NC3_NC3") (pintype "no_connect"))
    )
    (net (code "160") (name "unconnected-(U$1-PadNC4)") (class "Default")
      (node (ref "U$1") (pin "NC4") (pinfunction "NC4_NC4") (pintype "no_connect"))
    )
    (net (code "161") (name "unconnected-(U$1-PadNC5-PD8)") (class "Default")
      (node (ref "U$1") (pin "NC5-PD8") (pinfunction "NC5-PD8_NC5-PD8") (pintype "bidirectional"))
    )
    (net (code "162") (name "unconnected-(U$1-PadNC6-PB11)") (class "Default")
      (node (ref "U$1") (pin "NC6-PB11") (pinfunction "NC6-PB11_NC6-PB11") (pintype "no_connect"))
    )
    (net (code "163") (name "unconnected-(U$1-PadNC7-PF5)") (class "Default")
      (node (ref "U$1") (pin "NC7-PF5") (pinfunction "NC7-PF5_NC7-PF5") (pintype "bidirectional"))
    )
    (net (code "164") (name "unconnected-(U$1-PadNC8-PF4)") (class "Default")
      (node (ref "U$1") (pin "NC8-PF4") (pinfunction "NC8-PF4_NC8-PF4") (pintype "bidirectional"))
    )
    (net (code "165") (name "unconnected-(U$1-PadNRESET)") (class "Default")
      (node (ref "U$1") (pin "NRESET") (pinfunction "NRESET_NRESET") (pintype "input"))
    )
    (net (code "166") (name "unconnected-(U$1-PadPA1)") (class "Default")
      (node (ref "U$1") (pin "PA1") (pinfunction "PA1_PA1") (pintype "bidirectional"))
    )
    (net (code "167") (name "unconnected-(U$1-PadPA2)") (class "Default")
      (node (ref "U$1") (pin "PA2") (pinfunction "PA2_PA2") (pintype "bidirectional"))
    )
    (net (code "168") (name "unconnected-(U$1-PadPA3)") (class "Default")
      (node (ref "U$1") (pin "PA3") (pinfunction "PA3_PA3") (pintype "bidirectional"))
    )
    (net (code "169") (name "unconnected-(U$1-PadPA5)") (class "Default")
      (node (ref "U$1") (pin "PA5") (pinfunction "PA5_PA5") (pintype "bidirectional"))
    )
    (net (code "170") (name "unconnected-(U$1-PadPA7)") (class "Default")
      (node (ref "U$1") (pin "PA7") (pinfunction "PA7_PA7") (pintype "bidirectional"))
    )
    (net (code "171") (name "unconnected-(U$1-PadPA9)") (class "Default")
      (node (ref "U$1") (pin "PA9") (pinfunction "PA9_PA9") (pintype "bidirectional"))
    )
    (net (code "172") (name "unconnected-(U$1-PadPA10)") (class "Default")
      (node (ref "U$1") (pin "PA10") (pinfunction "PA10_PA10") (pintype "bidirectional"))
    )
    (net (code "173") (name "unconnected-(U$1-PadPA11)") (class "Default")
      (node (ref "U$1") (pin "PA11") (pinfunction "PA11_PA11") (pintype "bidirectional"))
    )
    (net (code "174") (name "unconnected-(U$1-PadPA12)") (class "Default")
      (node (ref "U$1") (pin "PA12") (pinfunction "PA12_PA12") (pintype "bidirectional"))
    )
    (net (code "175") (name "unconnected-(U$1-PadPA13)") (class "Default")
      (node (ref "U$1") (pin "PA13") (pinfunction "PA13_PA13") (pintype "bidirectional"))
    )
    (net (code "176") (name "unconnected-(U$1-PadPA14)") (class "Default")
      (node (ref "U$1") (pin "PA14") (pinfunction "PA14_PA14") (pintype "bidirectional"))
    )
    (net (code "177") (name "unconnected-(U$1-PadPB0)") (class "Default")
      (node (ref "U$1") (pin "PB0") (pinfunction "PB0_PB0") (pintype "bidirectional"))
    )
    (net (code "178") (name "unconnected-(U$1-PadPB13)") (class "Default")
      (node (ref "U$1") (pin "PB13") (pinfunction "PB13_PB13") (pintype "bidirectional"))
    )
    (net (code "179") (name "unconnected-(U$1-PadPC1)") (class "Default")
      (node (ref "U$1") (pin "PC1") (pinfunction "PC1_PC1") (pintype "bidirectional"))
    )
    (net (code "180") (name "unconnected-(U$1-PadPC4)") (class "Default")
      (node (ref "U$1") (pin "PC4") (pinfunction "PC4_PC4") (pintype "bidirectional"))
    )
    (net (code "181") (name "unconnected-(U$1-PadPC5)") (class "Default")
      (node (ref "U$1") (pin "PC5") (pinfunction "PC5_PC5") (pintype "bidirectional"))
    )
    (net (code "182") (name "unconnected-(U$1-PadPC13)") (class "Default")
      (node (ref "U$1") (pin "PC13") (pinfunction "PC13_PC13") (pintype "bidirectional"))
    )
    (net (code "183") (name "unconnected-(U$1-PadPC14)") (class "Default")
      (node (ref "U$1") (pin "PC14") (pinfunction "PC14_PC14") (pintype "bidirectional"))
    )
    (net (code "184") (name "unconnected-(U$1-PadPC15)") (class "Default")
      (node (ref "U$1") (pin "PC15") (pinfunction "PC15_PC15") (pintype "bidirectional"))
    )
    (net (code "185") (name "unconnected-(U$1-PadPF0-PH0)") (class "Default")
      (node (ref "U$1") (pin "PF0-PH0") (pinfunction "PF0-PH0_PF0-PH0") (pintype "bidirectional"))
    )
  )
)
